# display_driver_rev_B.net
KiCad netlist of a schematic drawn in EAGLE
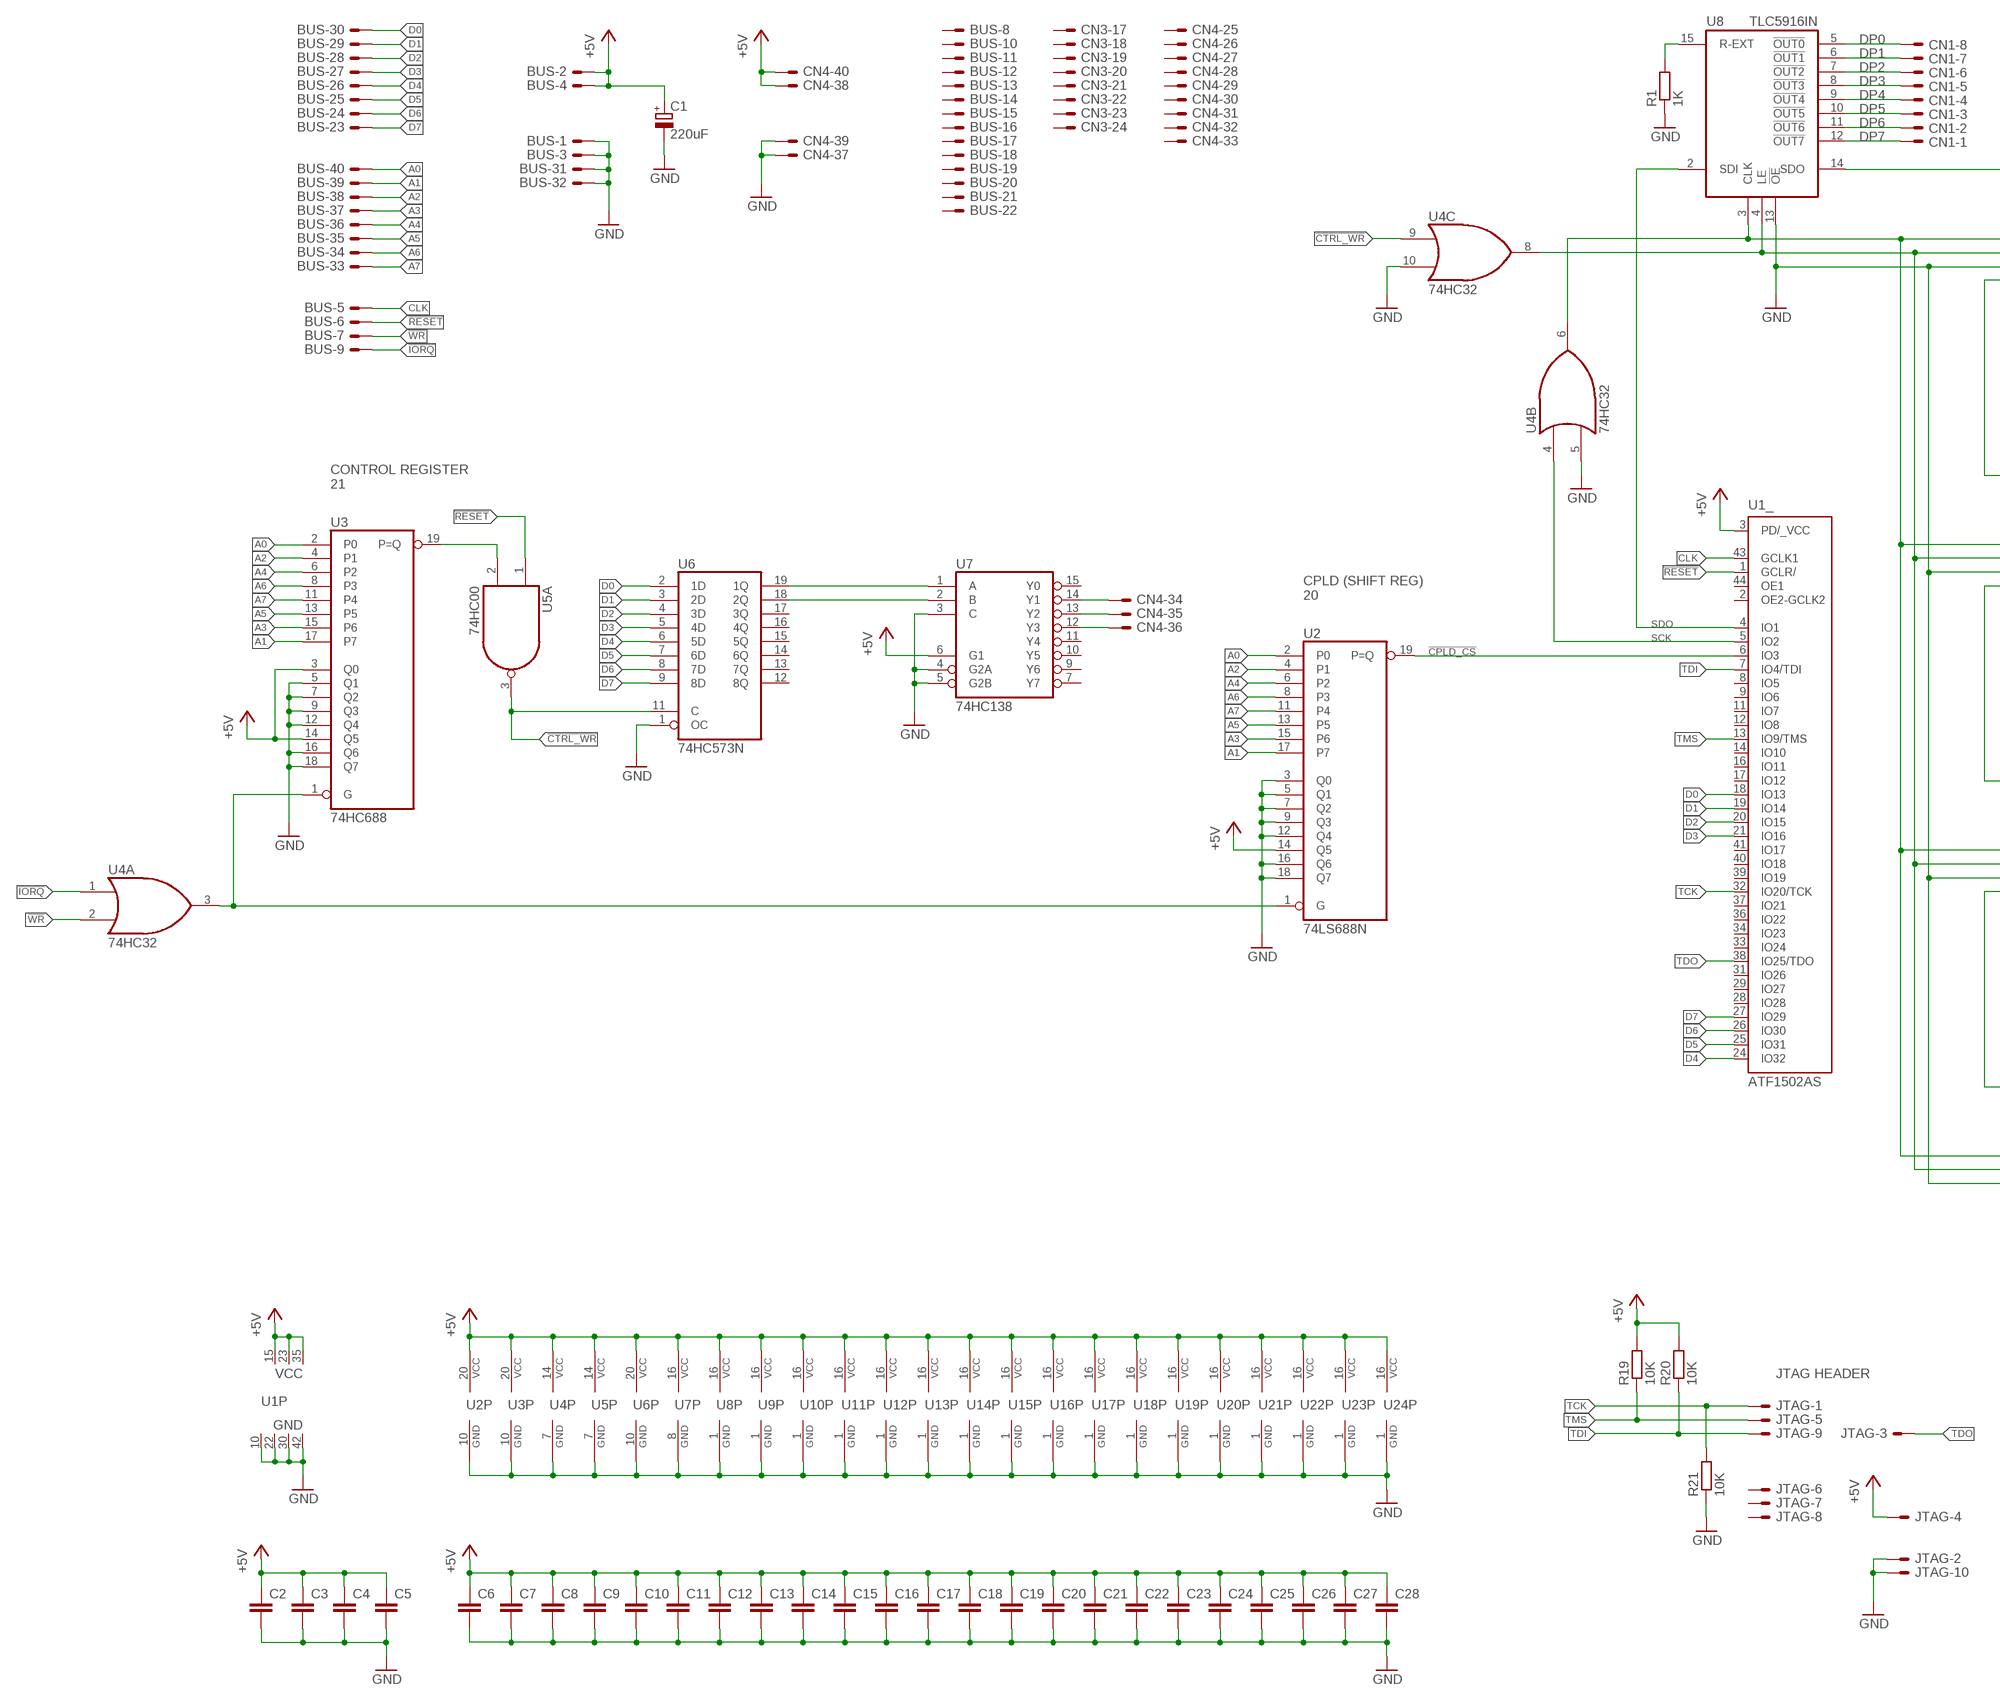
[diagram p0: schematic, sheet 1, part 1 of 2]
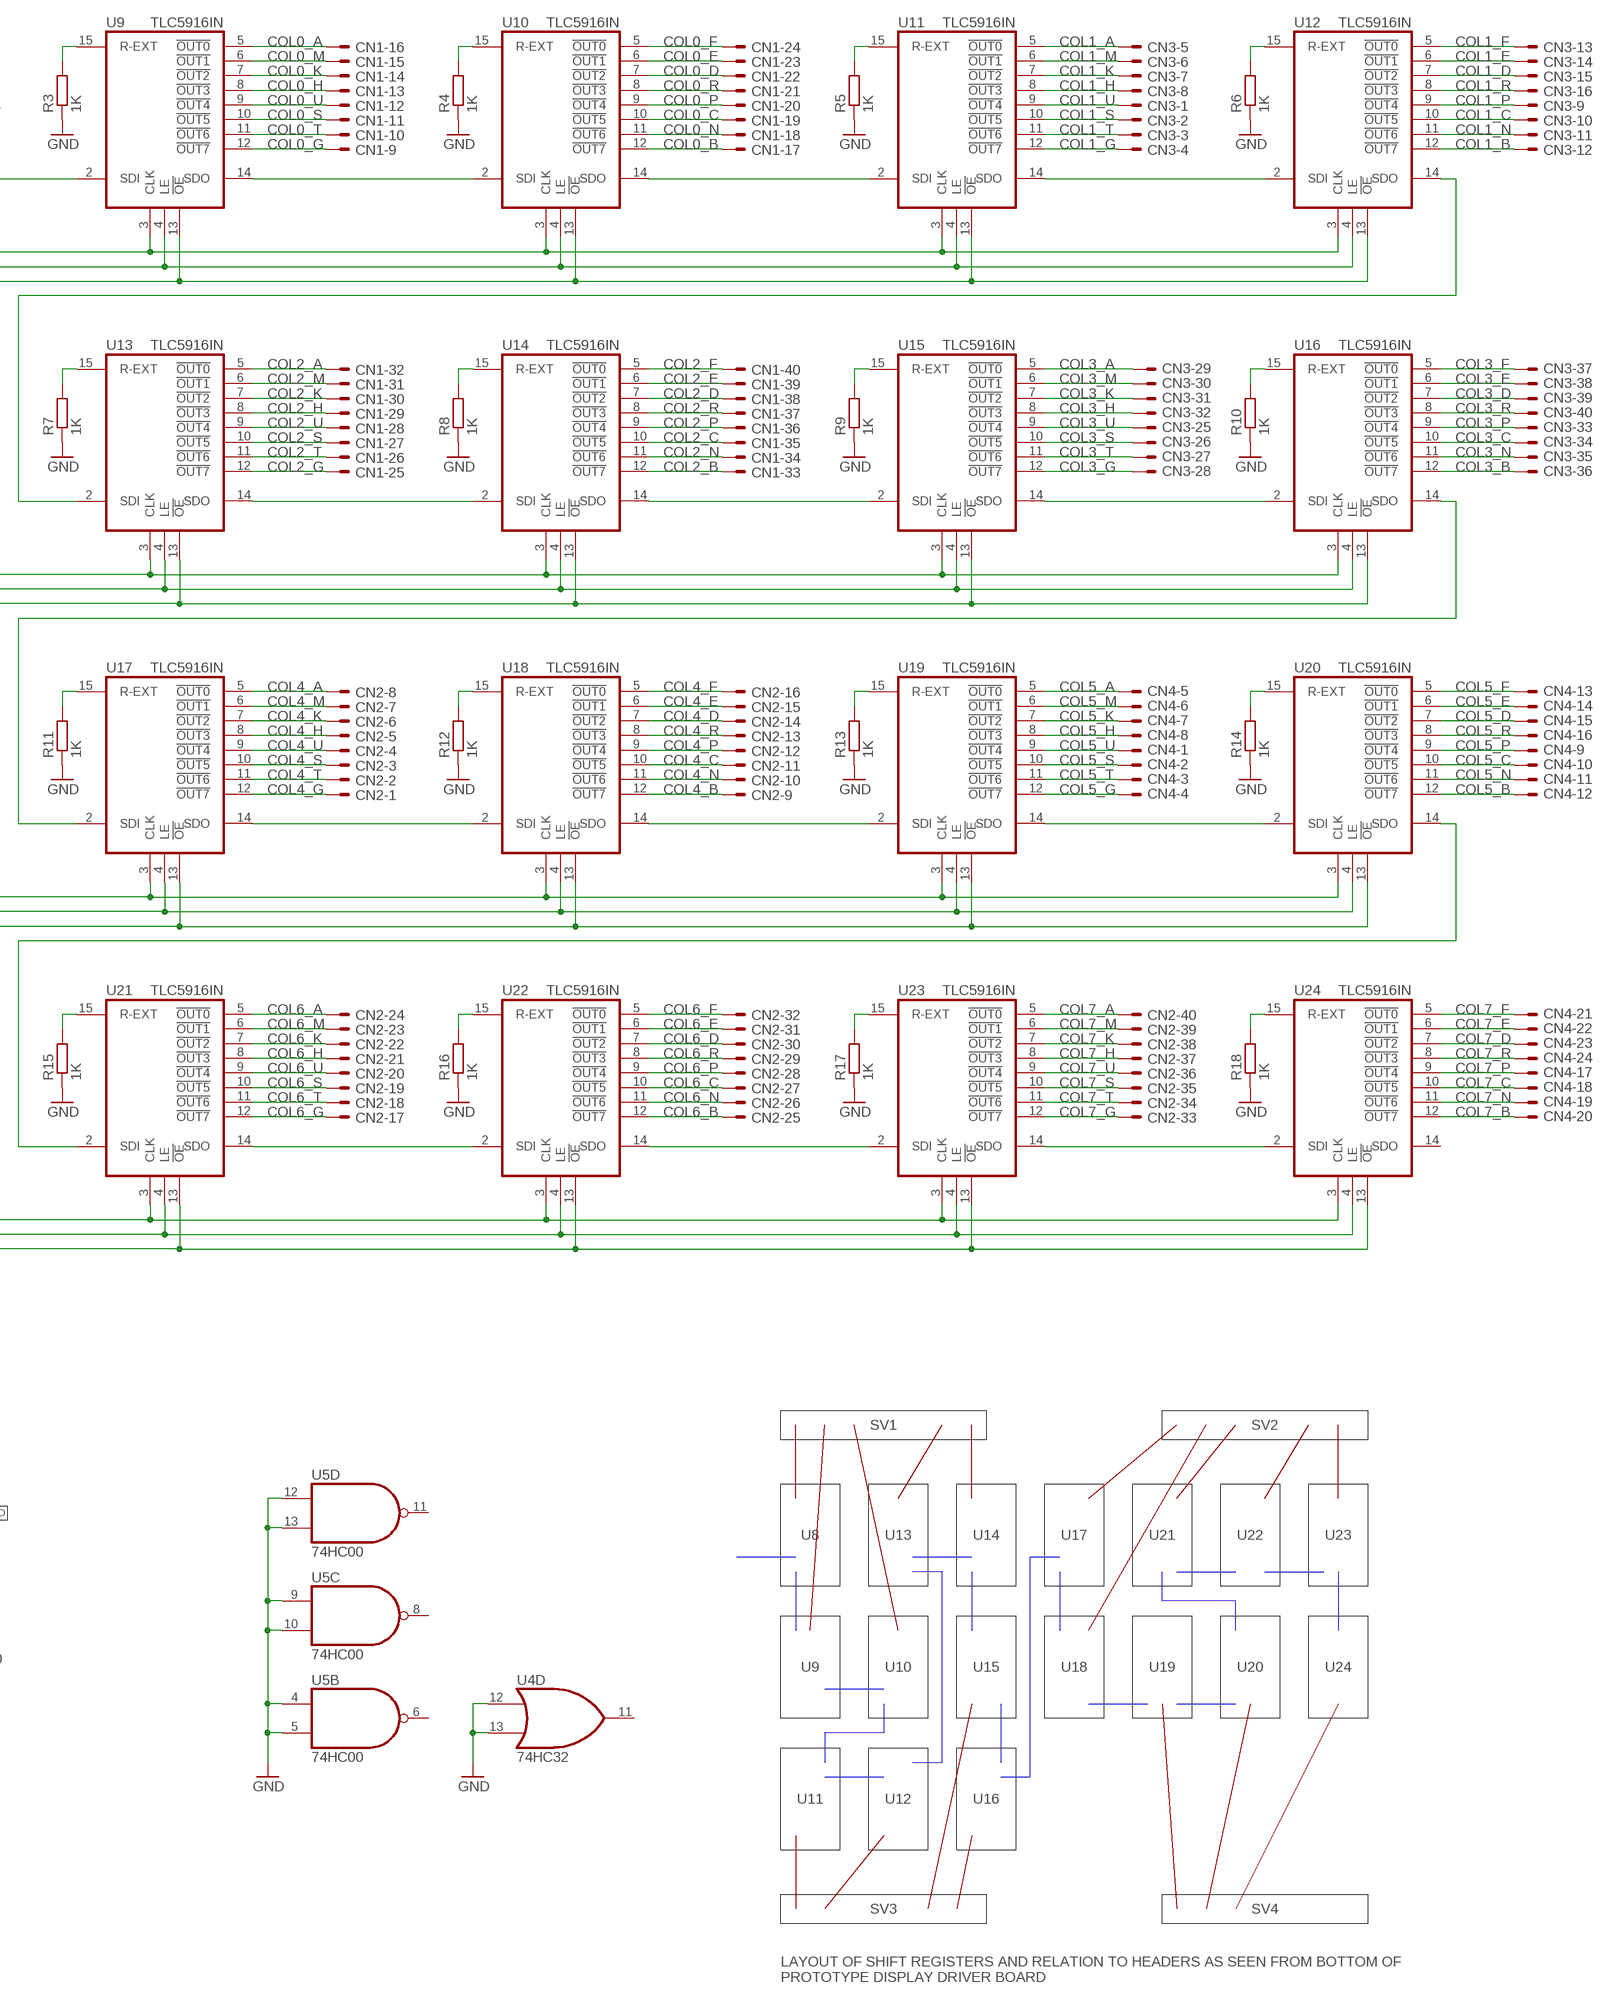
[diagram p1: schematic, sheet 1, part 2 of 2]

(export (version "E")
  (design (tool "Eeschema 10.0.6"))
  (components
    (comp (ref "BUS")
      (value "HDR40")
      (footprint "eagle-import:HDR40")
      (libsource (lib "eagle-import") (part "HDR40"))
    )
    (comp (ref "C1")
      (value "220uF")
      (footprint "eagle-import:E3,5-8")
      (libsource (lib "eagle-import") (part "CPOL-EUE3.5-8"))
    )
    (comp (ref "C2")
      (value "C-EU050-025X075")
      (footprint "eagle-import:C050-025X075")
      (libsource (lib "eagle-import") (part "C-EU050-025X075"))
    )
    (comp (ref "C3")
      (value "C-EU050-025X075")
      (footprint "eagle-import:C050-025X075")
      (libsource (lib "eagle-import") (part "C-EU050-025X075"))
    )
    (comp (ref "C4")
      (value "C-EU050-025X075")
      (footprint "eagle-import:C050-025X075")
      (libsource (lib "eagle-import") (part "C-EU050-025X075"))
    )
    (comp (ref "C5")
      (value "C-EU050-025X075")
      (footprint "eagle-import:C050-025X075")
      (libsource (lib "eagle-import") (part "C-EU050-025X075"))
    )
    (comp (ref "C6")
      (value "C-EU050-025X075")
      (footprint "eagle-import:C050-025X075")
      (libsource (lib "eagle-import") (part "C-EU050-025X075"))
    )
    (comp (ref "C7")
      (value "C-EU050-025X075")
      (footprint "eagle-import:C050-025X075")
      (libsource (lib "eagle-import") (part "C-EU050-025X075"))
    )
    (comp (ref "C8")
      (value "C-EU050-025X075")
      (footprint "eagle-import:C050-025X075")
      (libsource (lib "eagle-import") (part "C-EU050-025X075"))
    )
    (comp (ref "C9")
      (value "C-EU050-025X075")
      (footprint "eagle-import:C050-025X075")
      (libsource (lib "eagle-import") (part "C-EU050-025X075"))
    )
    (comp (ref "C10")
      (value "C-EU050-025X075")
      (footprint "eagle-import:C050-025X075")
      (libsource (lib "eagle-import") (part "C-EU050-025X075"))
    )
    (comp (ref "C11")
      (value "C-EU050-025X075")
      (footprint "eagle-import:C050-025X075")
      (libsource (lib "eagle-import") (part "C-EU050-025X075"))
    )
    (comp (ref "C12")
      (value "C-EU050-025X075")
      (footprint "eagle-import:C050-025X075")
      (libsource (lib "eagle-import") (part "C-EU050-025X075"))
    )
    (comp (ref "C13")
      (value "C-EU050-025X075")
      (footprint "eagle-import:C050-025X075")
      (libsource (lib "eagle-import") (part "C-EU050-025X075"))
    )
    (comp (ref "C14")
      (value "C-EU050-025X075")
      (footprint "eagle-import:C050-025X075")
      (libsource (lib "eagle-import") (part "C-EU050-025X075"))
    )
    (comp (ref "C15")
      (value "C-EU050-025X075")
      (footprint "eagle-import:C050-025X075")
      (libsource (lib "eagle-import") (part "C-EU050-025X075"))
    )
    (comp (ref "C16")
      (value "C-EU050-025X075")
      (footprint "eagle-import:C050-025X075")
      (libsource (lib "eagle-import") (part "C-EU050-025X075"))
    )
    (comp (ref "C17")
      (value "C-EU050-025X075")
      (footprint "eagle-import:C050-025X075")
      (libsource (lib "eagle-import") (part "C-EU050-025X075"))
    )
    (comp (ref "C18")
      (value "C-EU050-025X075")
      (footprint "eagle-import:C050-025X075")
      (libsource (lib "eagle-import") (part "C-EU050-025X075"))
    )
    (comp (ref "C19")
      (value "C-EU050-025X075")
      (footprint "eagle-import:C050-025X075")
      (libsource (lib "eagle-import") (part "C-EU050-025X075"))
    )
    (comp (ref "C20")
      (value "C-EU050-025X075")
      (footprint "eagle-import:C050-025X075")
      (libsource (lib "eagle-import") (part "C-EU050-025X075"))
    )
    (comp (ref "C21")
      (value "C-EU050-025X075")
      (footprint "eagle-import:C050-025X075")
      (libsource (lib "eagle-import") (part "C-EU050-025X075"))
    )
    (comp (ref "C22")
      (value "C-EU050-025X075")
      (footprint "eagle-import:C050-025X075")
      (libsource (lib "eagle-import") (part "C-EU050-025X075"))
    )
    (comp (ref "C23")
      (value "C-EU050-025X075")
      (footprint "eagle-import:C050-025X075")
      (libsource (lib "eagle-import") (part "C-EU050-025X075"))
    )
    (comp (ref "C24")
      (value "C-EU050-025X075")
      (footprint "eagle-import:C050-025X075")
      (libsource (lib "eagle-import") (part "C-EU050-025X075"))
    )
    (comp (ref "C25")
      (value "C-EU050-025X075")
      (footprint "eagle-import:C050-025X075")
      (libsource (lib "eagle-import") (part "C-EU050-025X075"))
    )
    (comp (ref "C26")
      (value "C-EU050-025X075")
      (footprint "eagle-import:C050-025X075")
      (libsource (lib "eagle-import") (part "C-EU050-025X075"))
    )
    (comp (ref "C27")
      (value "C-EU050-025X075")
      (footprint "eagle-import:C050-025X075")
      (libsource (lib "eagle-import") (part "C-EU050-025X075"))
    )
    (comp (ref "C28")
      (value "C-EU050-025X075")
      (footprint "eagle-import:C050-025X075")
      (libsource (lib "eagle-import") (part "C-EU050-025X075"))
    )
    (comp (ref "CN1")
      (value "HDR40")
      (footprint "eagle-import:HDR40")
      (libsource (lib "eagle-import") (part "HDR40"))
    )
    (comp (ref "CN2")
      (value "HDR40")
      (footprint "eagle-import:HDR40")
      (libsource (lib "eagle-import") (part "HDR40"))
    )
    (comp (ref "CN3")
      (value "HDR40")
      (footprint "eagle-import:HDR40")
      (libsource (lib "eagle-import") (part "HDR40"))
    )
    (comp (ref "CN4")
      (value "HDR40")
      (footprint "eagle-import:HDR40")
      (libsource (lib "eagle-import") (part "HDR40"))
    )
    (comp (ref "JTAG")
      (value "ML10E")
      (footprint "eagle-import:ML10")
      (libsource (lib "eagle-import") (part "ML10E"))
    )
    (comp (ref "R1")
      (value "1K")
      (footprint "eagle-import:0207_10")
      (libsource (lib "eagle-import") (part "R-EU_0207/10"))
    )
    (comp (ref "R3")
      (value "1K")
      (footprint "eagle-import:0207_10")
      (libsource (lib "eagle-import") (part "R-EU_0207/10"))
    )
    (comp (ref "R4")
      (value "1K")
      (footprint "eagle-import:0207_10")
      (libsource (lib "eagle-import") (part "R-EU_0207/10"))
    )
    (comp (ref "R5")
      (value "1K")
      (footprint "eagle-import:0207_10")
      (libsource (lib "eagle-import") (part "R-EU_0207/10"))
    )
    (comp (ref "R6")
      (value "1K")
      (footprint "eagle-import:0207_10")
      (libsource (lib "eagle-import") (part "R-EU_0207/10"))
    )
    (comp (ref "R7")
      (value "1K")
      (footprint "eagle-import:0207_10")
      (libsource (lib "eagle-import") (part "R-EU_0207/10"))
    )
    (comp (ref "R8")
      (value "1K")
      (footprint "eagle-import:0207_10")
      (libsource (lib "eagle-import") (part "R-EU_0207/10"))
    )
    (comp (ref "R9")
      (value "1K")
      (footprint "eagle-import:0207_10")
      (libsource (lib "eagle-import") (part "R-EU_0207/10"))
    )
    (comp (ref "R10")
      (value "1K")
      (footprint "eagle-import:0207_10")
      (libsource (lib "eagle-import") (part "R-EU_0207/10"))
    )
    (comp (ref "R11")
      (value "1K")
      (footprint "eagle-import:0207_10")
      (libsource (lib "eagle-import") (part "R-EU_0207/10"))
    )
    (comp (ref "R12")
      (value "1K")
      (footprint "eagle-import:0207_10")
      (libsource (lib "eagle-import") (part "R-EU_0207/10"))
    )
    (comp (ref "R13")
      (value "1K")
      (footprint "eagle-import:0207_10")
      (libsource (lib "eagle-import") (part "R-EU_0207/10"))
    )
    (comp (ref "R14")
      (value "1K")
      (footprint "eagle-import:0207_10")
      (libsource (lib "eagle-import") (part "R-EU_0207/10"))
    )
    (comp (ref "R15")
      (value "1K")
      (footprint "eagle-import:0207_10")
      (libsource (lib "eagle-import") (part "R-EU_0207/10"))
    )
    (comp (ref "R16")
      (value "1K")
      (footprint "eagle-import:0207_10")
      (libsource (lib "eagle-import") (part "R-EU_0207/10"))
    )
    (comp (ref "R17")
      (value "1K")
      (footprint "eagle-import:0207_10")
      (libsource (lib "eagle-import") (part "R-EU_0207/10"))
    )
    (comp (ref "R18")
      (value "1K")
      (footprint "eagle-import:0207_10")
      (libsource (lib "eagle-import") (part "R-EU_0207/10"))
    )
    (comp (ref "R19")
      (value "10K")
      (footprint "eagle-import:0207_10")
      (libsource (lib "eagle-import") (part "R-EU_0207/10"))
    )
    (comp (ref "R20")
      (value "10K")
      (footprint "eagle-import:0207_10")
      (libsource (lib "eagle-import") (part "R-EU_0207/10"))
    )
    (comp (ref "R21")
      (value "10K")
      (footprint "eagle-import:0207_10")
      (libsource (lib "eagle-import") (part "R-EU_0207/10"))
    )
    (comp (ref "U1")
      (value "ATF1502AS")
      (footprint "eagle-import:PLCC-S44")
      (fields (field (name "MPN") "EPM7032SLC44-6N"))
      (libsource (lib "eagle-import") (part "EPM7032S44"))
    )
    (comp (ref "U2")
      (value "74LS688N")
      (footprint "eagle-import:DIL20")
      (libsource (lib "eagle-import") (part "74688NLS"))
    )
    (comp (ref "U3")
      (value "74HC688")
      (footprint "eagle-import:DIL20")
      (libsource (lib "eagle-import") (part "74688NLS"))
    )
    (comp (ref "U4")
      (value "74HC32")
      (footprint "eagle-import:DIL14")
      (libsource (lib "eagle-import") (part "7432NLS"))
    )
    (comp (ref "U5")
      (value "74HC00")
      (footprint "eagle-import:DIL14")
      (libsource (lib "eagle-import") (part "7400NLS"))
    )
    (comp (ref "U6")
      (value "74HC573N")
      (footprint "eagle-import:DIL20")
      (libsource (lib "eagle-import") (part "74573NHC"))
    )
    (comp (ref "U7")
      (value "74HC138")
      (footprint "eagle-import:DIL16")
      (libsource (lib "eagle-import") (part "74138NLS"))
    )
    (comp (ref "U8")
      (value "TLC5916IN")
      (footprint "eagle-import:DIL16")
      (libsource (lib "eagle-import") (part "TLC5916IN"))
    )
    (comp (ref "U9")
      (value "TLC5916IN")
      (footprint "eagle-import:DIL16")
      (libsource (lib "eagle-import") (part "TLC5916IN"))
    )
    (comp (ref "U10")
      (value "TLC5916IN")
      (footprint "eagle-import:DIL16")
      (libsource (lib "eagle-import") (part "TLC5916IN"))
    )
    (comp (ref "U11")
      (value "TLC5916IN")
      (footprint "eagle-import:DIL16")
      (libsource (lib "eagle-import") (part "TLC5916IN"))
    )
    (comp (ref "U12")
      (value "TLC5916IN")
      (footprint "eagle-import:DIL16")
      (libsource (lib "eagle-import") (part "TLC5916IN"))
    )
    (comp (ref "U13")
      (value "TLC5916IN")
      (footprint "eagle-import:DIL16")
      (libsource (lib "eagle-import") (part "TLC5916IN"))
    )
    (comp (ref "U14")
      (value "TLC5916IN")
      (footprint "eagle-import:DIL16")
      (libsource (lib "eagle-import") (part "TLC5916IN"))
    )
    (comp (ref "U15")
      (value "TLC5916IN")
      (footprint "eagle-import:DIL16")
      (libsource (lib "eagle-import") (part "TLC5916IN"))
    )
    (comp (ref "U16")
      (value "TLC5916IN")
      (footprint "eagle-import:DIL16")
      (libsource (lib "eagle-import") (part "TLC5916IN"))
    )
    (comp (ref "U17")
      (value "TLC5916IN")
      (footprint "eagle-import:DIL16")
      (libsource (lib "eagle-import") (part "TLC5916IN"))
    )
    (comp (ref "U18")
      (value "TLC5916IN")
      (footprint "eagle-import:DIL16")
      (libsource (lib "eagle-import") (part "TLC5916IN"))
    )
    (comp (ref "U19")
      (value "TLC5916IN")
      (footprint "eagle-import:DIL16")
      (libsource (lib "eagle-import") (part "TLC5916IN"))
    )
    (comp (ref "U20")
      (value "TLC5916IN")
      (footprint "eagle-import:DIL16")
      (libsource (lib "eagle-import") (part "TLC5916IN"))
    )
    (comp (ref "U21")
      (value "TLC5916IN")
      (footprint "eagle-import:DIL16")
      (libsource (lib "eagle-import") (part "TLC5916IN"))
    )
    (comp (ref "U22")
      (value "TLC5916IN")
      (footprint "eagle-import:DIL16")
      (libsource (lib "eagle-import") (part "TLC5916IN"))
    )
    (comp (ref "U23")
      (value "TLC5916IN")
      (footprint "eagle-import:DIL16")
      (libsource (lib "eagle-import") (part "TLC5916IN"))
    )
    (comp (ref "U24")
      (value "TLC5916IN")
      (footprint "eagle-import:DIL16")
      (libsource (lib "eagle-import") (part "TLC5916IN"))
    )
  )
  (nets
    (net (code "1") (name "+5V") (class "Default")
      (node (ref "BUS") (pin "2") (pinfunction "S_2") (pintype "passive"))
      (node (ref "BUS") (pin "4") (pinfunction "S_4") (pintype "passive"))
      (node (ref "C1") (pin "+") (pinfunction "+_+") (pintype "passive"))
      (node (ref "C10") (pin "1") (pinfunction "1_1") (pintype "passive"))
      (node (ref "C11") (pin "1") (pinfunction "1_1") (pintype "passive"))
      (node (ref "C12") (pin "1") (pinfunction "1_1") (pintype "passive"))
      (node (ref "C13") (pin "1") (pinfunction "1_1") (pintype "passive"))
      (node (ref "C14") (pin "1") (pinfunction "1_1") (pintype "passive"))
      (node (ref "C15") (pin "1") (pinfunction "1_1") (pintype "passive"))
      (node (ref "C16") (pin "1") (pinfunction "1_1") (pintype "passive"))
      (node (ref "C17") (pin "1") (pinfunction "1_1") (pintype "passive"))
      (node (ref "C18") (pin "1") (pinfunction "1_1") (pintype "passive"))
      (node (ref "C19") (pin "1") (pinfunction "1_1") (pintype "passive"))
      (node (ref "C2") (pin "1") (pinfunction "1_1") (pintype "passive"))
      (node (ref "C20") (pin "1") (pinfunction "1_1") (pintype "passive"))
      (node (ref "C21") (pin "1") (pinfunction "1_1") (pintype "passive"))
      (node (ref "C22") (pin "1") (pinfunction "1_1") (pintype "passive"))
      (node (ref "C23") (pin "1") (pinfunction "1_1") (pintype "passive"))
      (node (ref "C24") (pin "1") (pinfunction "1_1") (pintype "passive"))
      (node (ref "C25") (pin "1") (pinfunction "1_1") (pintype "passive"))
      (node (ref "C26") (pin "1") (pinfunction "1_1") (pintype "passive"))
      (node (ref "C27") (pin "1") (pinfunction "1_1") (pintype "passive"))
      (node (ref "C28") (pin "1") (pinfunction "1_1") (pintype "passive"))
      (node (ref "C3") (pin "1") (pinfunction "1_1") (pintype "passive"))
      (node (ref "C4") (pin "1") (pinfunction "1_1") (pintype "passive"))
      (node (ref "C5") (pin "1") (pinfunction "1_1") (pintype "passive"))
      (node (ref "C6") (pin "1") (pinfunction "1_1") (pintype "passive"))
      (node (ref "C7") (pin "1") (pinfunction "1_1") (pintype "passive"))
      (node (ref "C8") (pin "1") (pinfunction "1_1") (pintype "passive"))
      (node (ref "C9") (pin "1") (pinfunction "1_1") (pintype "passive"))
      (node (ref "CN4") (pin "38") (pinfunction "S_38") (pintype "passive"))
      (node (ref "CN4") (pin "40") (pinfunction "S_40") (pintype "passive"))
      (node (ref "JTAG") (pin "4") (pinfunction "S_4") (pintype "passive"))
      (node (ref "R19") (pin "2") (pinfunction "2_2") (pintype "passive"))
      (node (ref "R20") (pin "2") (pinfunction "2_2") (pintype "passive"))
      (node (ref "U1") (pin "15") (pinfunction "VCC_15") (pintype "power_in"))
      (node (ref "U1") (pin "23") (pinfunction "VCC_23") (pintype "power_in"))
      (node (ref "U1") (pin "3") (pinfunction "PD/_VCC_3") (pintype "passive"))
      (node (ref "U1") (pin "35") (pinfunction "VCC_35") (pintype "power_in"))
      (node (ref "U10") (pin "16") (pinfunction "VCC_16") (pintype "power_in"))
      (node (ref "U11") (pin "16") (pinfunction "VCC_16") (pintype "power_in"))
      (node (ref "U12") (pin "16") (pinfunction "VCC_16") (pintype "power_in"))
      (node (ref "U13") (pin "16") (pinfunction "VCC_16") (pintype "power_in"))
      (node (ref "U14") (pin "16") (pinfunction "VCC_16") (pintype "power_in"))
      (node (ref "U15") (pin "16") (pinfunction "VCC_16") (pintype "power_in"))
      (node (ref "U16") (pin "16") (pinfunction "VCC_16") (pintype "power_in"))
      (node (ref "U17") (pin "16") (pinfunction "VCC_16") (pintype "power_in"))
      (node (ref "U18") (pin "16") (pinfunction "VCC_16") (pintype "power_in"))
      (node (ref "U19") (pin "16") (pinfunction "VCC_16") (pintype "power_in"))
      (node (ref "U2") (pin "14") (pinfunction "Q5_14") (pintype "input"))
      (node (ref "U2") (pin "20") (pinfunction "VCC_20") (pintype "power_in"))
      (node (ref "U20") (pin "16") (pinfunction "VCC_16") (pintype "power_in"))
      (node (ref "U21") (pin "16") (pinfunction "VCC_16") (pintype "power_in"))
      (node (ref "U22") (pin "16") (pinfunction "VCC_16") (pintype "power_in"))
      (node (ref "U23") (pin "16") (pinfunction "VCC_16") (pintype "power_in"))
      (node (ref "U24") (pin "16") (pinfunction "VCC_16") (pintype "power_in"))
      (node (ref "U3") (pin "14") (pinfunction "Q5_14") (pintype "input"))
      (node (ref "U3") (pin "20") (pinfunction "VCC_20") (pintype "power_in"))
      (node (ref "U3") (pin "3") (pinfunction "Q0_3") (pintype "input"))
      (node (ref "U4") (pin "14") (pinfunction "VCC_14") (pintype "power_in"))
      (node (ref "U5") (pin "14") (pinfunction "VCC_14") (pintype "power_in"))
      (node (ref "U6") (pin "20") (pinfunction "VCC_20") (pintype "power_in"))
      (node (ref "U7") (pin "16") (pinfunction "VCC_16") (pintype "power_in"))
      (node (ref "U7") (pin "6") (pinfunction "G1_6") (pintype "input"))
      (node (ref "U8") (pin "16") (pinfunction "VCC_16") (pintype "power_in"))
      (node (ref "U9") (pin "16") (pinfunction "VCC_16") (pintype "power_in"))
    )
    (net (code "2") (name "/COL0_A") (class "Default")
      (node (ref "CN1") (pin "16") (pinfunction "S_16") (pintype "passive"))
      (node (ref "U9") (pin "5") (pinfunction "~{OUT0}_5") (pintype "open_collector"))
    )
    (net (code "3") (name "/COL0_B") (class "Default")
      (node (ref "CN1") (pin "17") (pinfunction "S_17") (pintype "passive"))
      (node (ref "U10") (pin "12") (pinfunction "~{OUT7}_12") (pintype "open_collector"))
    )
    (net (code "4") (name "/COL0_C") (class "Default")
      (node (ref "CN1") (pin "19") (pinfunction "S_19") (pintype "passive"))
      (node (ref "U10") (pin "10") (pinfunction "~{OUT5}_10") (pintype "open_collector"))
    )
    (net (code "5") (name "/COL0_D") (class "Default")
      (node (ref "CN1") (pin "22") (pinfunction "S_22") (pintype "passive"))
      (node (ref "U10") (pin "7") (pinfunction "~{OUT2}_7") (pintype "open_collector"))
    )
    (net (code "6") (name "/COL0_E") (class "Default")
      (node (ref "CN1") (pin "23") (pinfunction "S_23") (pintype "passive"))
      (node (ref "U10") (pin "6") (pinfunction "~{OUT1}_6") (pintype "open_collector"))
    )
    (net (code "7") (name "/COL0_F") (class "Default")
      (node (ref "CN1") (pin "24") (pinfunction "S_24") (pintype "passive"))
      (node (ref "U10") (pin "5") (pinfunction "~{OUT0}_5") (pintype "open_collector"))
    )
    (net (code "8") (name "/COL0_G") (class "Default")
      (node (ref "CN1") (pin "9") (pinfunction "S_9") (pintype "passive"))
      (node (ref "U9") (pin "12") (pinfunction "~{OUT7}_12") (pintype "open_collector"))
    )
    (net (code "9") (name "/COL0_H") (class "Default")
      (node (ref "CN1") (pin "13") (pinfunction "S_13") (pintype "passive"))
      (node (ref "U9") (pin "8") (pinfunction "~{OUT3}_8") (pintype "open_collector"))
    )
    (net (code "10") (name "/COL0_K") (class "Default")
      (node (ref "CN1") (pin "14") (pinfunction "S_14") (pintype "passive"))
      (node (ref "U9") (pin "7") (pinfunction "~{OUT2}_7") (pintype "open_collector"))
    )
    (net (code "11") (name "/COL0_M") (class "Default")
      (node (ref "CN1") (pin "15") (pinfunction "S_15") (pintype "passive"))
      (node (ref "U9") (pin "6") (pinfunction "~{OUT1}_6") (pintype "open_collector"))
    )
    (net (code "12") (name "/COL0_N") (class "Default")
      (node (ref "CN1") (pin "18") (pinfunction "S_18") (pintype "passive"))
      (node (ref "U10") (pin "11") (pinfunction "~{OUT6}_11") (pintype "open_collector"))
    )
    (net (code "13") (name "/COL0_P") (class "Default")
      (node (ref "CN1") (pin "20") (pinfunction "S_20") (pintype "passive"))
      (node (ref "U10") (pin "9") (pinfunction "~{OUT4}_9") (pintype "open_collector"))
    )
    (net (code "14") (name "/COL0_R") (class "Default")
      (node (ref "CN1") (pin "21") (pinfunction "S_21") (pintype "passive"))
      (node (ref "U10") (pin "8") (pinfunction "~{OUT3}_8") (pintype "open_collector"))
    )
    (net (code "15") (name "/COL0_S") (class "Default")
      (node (ref "CN1") (pin "11") (pinfunction "S_11") (pintype "passive"))
      (node (ref "U9") (pin "10") (pinfunction "~{OUT5}_10") (pintype "open_collector"))
    )
    (net (code "16") (name "/COL0_T") (class "Default")
      (node (ref "CN1") (pin "10") (pinfunction "S_10") (pintype "passive"))
      (node (ref "U9") (pin "11") (pinfunction "~{OUT6}_11") (pintype "open_collector"))
    )
    (net (code "17") (name "/COL0_U") (class "Default")
      (node (ref "CN1") (pin "12") (pinfunction "S_12") (pintype "passive"))
      (node (ref "U9") (pin "9") (pinfunction "~{OUT4}_9") (pintype "open_collector"))
    )
    (net (code "18") (name "/COL1_A") (class "Default")
      (node (ref "CN3") (pin "5") (pinfunction "S_5") (pintype "passive"))
      (node (ref "U11") (pin "5") (pinfunction "~{OUT0}_5") (pintype "open_collector"))
    )
    (net (code "19") (name "/COL1_B") (class "Default")
      (node (ref "CN3") (pin "12") (pinfunction "S_12") (pintype "passive"))
      (node (ref "U12") (pin "12") (pinfunction "~{OUT7}_12") (pintype "open_collector"))
    )
    (net (code "20") (name "/COL1_C") (class "Default")
      (node (ref "CN3") (pin "10") (pinfunction "S_10") (pintype "passive"))
      (node (ref "U12") (pin "10") (pinfunction "~{OUT5}_10") (pintype "open_collector"))
    )
    (net (code "21") (name "/COL1_D") (class "Default")
      (node (ref "CN3") (pin "15") (pinfunction "S_15") (pintype "passive"))
      (node (ref "U12") (pin "7") (pinfunction "~{OUT2}_7") (pintype "open_collector"))
    )
    (net (code "22") (name "/COL1_E") (class "Default")
      (node (ref "CN3") (pin "14") (pinfunction "S_14") (pintype "passive"))
      (node (ref "U12") (pin "6") (pinfunction "~{OUT1}_6") (pintype "open_collector"))
    )
    (net (code "23") (name "/COL1_F") (class "Default")
      (node (ref "CN3") (pin "13") (pinfunction "S_13") (pintype "passive"))
      (node (ref "U12") (pin "5") (pinfunction "~{OUT0}_5") (pintype "open_collector"))
    )
    (net (code "24") (name "/COL1_G") (class "Default")
      (node (ref "CN3") (pin "4") (pinfunction "S_4") (pintype "passive"))
      (node (ref "U11") (pin "12") (pinfunction "~{OUT7}_12") (pintype "open_collector"))
    )
    (net (code "25") (name "/COL1_H") (class "Default")
      (node (ref "CN3") (pin "8") (pinfunction "S_8") (pintype "passive"))
      (node (ref "U11") (pin "8") (pinfunction "~{OUT3}_8") (pintype "open_collector"))
    )
    (net (code "26") (name "/COL1_K") (class "Default")
      (node (ref "CN3") (pin "7") (pinfunction "S_7") (pintype "passive"))
      (node (ref "U11") (pin "7") (pinfunction "~{OUT2}_7") (pintype "open_collector"))
    )
    (net (code "27") (name "/COL1_M") (class "Default")
      (node (ref "CN3") (pin "6") (pinfunction "S_6") (pintype "passive"))
      (node (ref "U11") (pin "6") (pinfunction "~{OUT1}_6") (pintype "open_collector"))
    )
    (net (code "28") (name "/COL1_N") (class "Default")
      (node (ref "CN3") (pin "11") (pinfunction "S_11") (pintype "passive"))
      (node (ref "U12") (pin "11") (pinfunction "~{OUT6}_11") (pintype "open_collector"))
    )
    (net (code "29") (name "/COL1_P") (class "Default")
      (node (ref "CN3") (pin "9") (pinfunction "S_9") (pintype "passive"))
      (node (ref "U12") (pin "9") (pinfunction "~{OUT4}_9") (pintype "open_collector"))
    )
    (net (code "30") (name "/COL1_R") (class "Default")
      (node (ref "CN3") (pin "16") (pinfunction "S_16") (pintype "passive"))
      (node (ref "U12") (pin "8") (pinfunction "~{OUT3}_8") (pintype "open_collector"))
    )
    (net (code "31") (name "/COL1_S") (class "Default")
      (node (ref "CN3") (pin "2") (pinfunction "S_2") (pintype "passive"))
      (node (ref "U11") (pin "10") (pinfunction "~{OUT5}_10") (pintype "open_collector"))
    )
    (net (code "32") (name "/COL1_T") (class "Default")
      (node (ref "CN3") (pin "3") (pinfunction "S_3") (pintype "passive"))
      (node (ref "U11") (pin "11") (pinfunction "~{OUT6}_11") (pintype "open_collector"))
    )
    (net (code "33") (name "/COL1_U") (class "Default")
      (node (ref "CN3") (pin "1") (pinfunction "S_1") (pintype "passive"))
      (node (ref "U11") (pin "9") (pinfunction "~{OUT4}_9") (pintype "open_collector"))
    )
    (net (code "34") (name "/COL2_A") (class "Default")
      (node (ref "CN1") (pin "32") (pinfunction "S_32") (pintype "passive"))
      (node (ref "U13") (pin "5") (pinfunction "~{OUT0}_5") (pintype "open_collector"))
    )
    (net (code "35") (name "/COL2_B") (class "Default")
      (node (ref "CN1") (pin "33") (pinfunction "S_33") (pintype "passive"))
      (node (ref "U14") (pin "12") (pinfunction "~{OUT7}_12") (pintype "open_collector"))
    )
    (net (code "36") (name "/COL2_C") (class "Default")
      (node (ref "CN1") (pin "35") (pinfunction "S_35") (pintype "passive"))
      (node (ref "U14") (pin "10") (pinfunction "~{OUT5}_10") (pintype "open_collector"))
    )
    (net (code "37") (name "/COL2_D") (class "Default")
      (node (ref "CN1") (pin "38") (pinfunction "S_38") (pintype "passive"))
      (node (ref "U14") (pin "7") (pinfunction "~{OUT2}_7") (pintype "open_collector"))
    )
    (net (code "38") (name "/COL2_E") (class "Default")
      (node (ref "CN1") (pin "39") (pinfunction "S_39") (pintype "passive"))
      (node (ref "U14") (pin "6") (pinfunction "~{OUT1}_6") (pintype "open_collector"))
    )
    (net (code "39") (name "/COL2_F") (class "Default")
      (node (ref "CN1") (pin "40") (pinfunction "S_40") (pintype "passive"))
      (node (ref "U14") (pin "5") (pinfunction "~{OUT0}_5") (pintype "open_collector"))
    )
    (net (code "40") (name "/COL2_G") (class "Default")
      (node (ref "CN1") (pin "25") (pinfunction "S_25") (pintype "passive"))
      (node (ref "U13") (pin "12") (pinfunction "~{OUT7}_12") (pintype "open_collector"))
    )
    (net (code "41") (name "/COL2_H") (class "Default")
      (node (ref "CN1") (pin "29") (pinfunction "S_29") (pintype "passive"))
      (node (ref "U13") (pin "8") (pinfunction "~{OUT3}_8") (pintype "open_collector"))
    )
    (net (code "42") (name "/COL2_K") (class "Default")
      (node (ref "CN1") (pin "30") (pinfunction "S_30") (pintype "passive"))
      (node (ref "U13") (pin "7") (pinfunction "~{OUT2}_7") (pintype "open_collector"))
    )
    (net (code "43") (name "/COL2_M") (class "Default")
      (node (ref "CN1") (pin "31") (pinfunction "S_31") (pintype "passive"))
      (node (ref "U13") (pin "6") (pinfunction "~{OUT1}_6") (pintype "open_collector"))
    )
    (net (code "44") (name "/COL2_N") (class "Default")
      (node (ref "CN1") (pin "34") (pinfunction "S_34") (pintype "passive"))
      (node (ref "U14") (pin "11") (pinfunction "~{OUT6}_11") (pintype "open_collector"))
    )
    (net (code "45") (name "/COL2_P") (class "Default")
      (node (ref "CN1") (pin "36") (pinfunction "S_36") (pintype "passive"))
      (node (ref "U14") (pin "9") (pinfunction "~{OUT4}_9") (pintype "open_collector"))
    )
    (net (code "46") (name "/COL2_R") (class "Default")
      (node (ref "CN1") (pin "37") (pinfunction "S_37") (pintype "passive"))
      (node (ref "U14") (pin "8") (pinfunction "~{OUT3}_8") (pintype "open_collector"))
    )
    (net (code "47") (name "/COL2_S") (class "Default")
      (node (ref "CN1") (pin "27") (pinfunction "S_27") (pintype "passive"))
      (node (ref "U13") (pin "10") (pinfunction "~{OUT5}_10") (pintype "open_collector"))
    )
    (net (code "48") (name "/COL2_T") (class "Default")
      (node (ref "CN1") (pin "26") (pinfunction "S_26") (pintype "passive"))
      (node (ref "U13") (pin "11") (pinfunction "~{OUT6}_11") (pintype "open_collector"))
    )
    (net (code "49") (name "/COL2_U") (class "Default")
      (node (ref "CN1") (pin "28") (pinfunction "S_28") (pintype "passive"))
      (node (ref "U13") (pin "9") (pinfunction "~{OUT4}_9") (pintype "open_collector"))
    )
    (net (code "50") (name "/COL3_A") (class "Default")
      (node (ref "CN3") (pin "29") (pinfunction "S_29") (pintype "passive"))
      (node (ref "U15") (pin "5") (pinfunction "~{OUT0}_5") (pintype "open_collector"))
    )
    (net (code "51") (name "/COL3_B") (class "Default")
      (node (ref "CN3") (pin "36") (pinfunction "S_36") (pintype "passive"))
      (node (ref "U16") (pin "12") (pinfunction "~{OUT7}_12") (pintype "open_collector"))
    )
    (net (code "52") (name "/COL3_C") (class "Default")
      (node (ref "CN3") (pin "34") (pinfunction "S_34") (pintype "passive"))
      (node (ref "U16") (pin "10") (pinfunction "~{OUT5}_10") (pintype "open_collector"))
    )
    (net (code "53") (name "/COL3_D") (class "Default")
      (node (ref "CN3") (pin "39") (pinfunction "S_39") (pintype "passive"))
      (node (ref "U16") (pin "7") (pinfunction "~{OUT2}_7") (pintype "open_collector"))
    )
    (net (code "54") (name "/COL3_E") (class "Default")
      (node (ref "CN3") (pin "38") (pinfunction "S_38") (pintype "passive"))
      (node (ref "U16") (pin "6") (pinfunction "~{OUT1}_6") (pintype "open_collector"))
    )
    (net (code "55") (name "/COL3_F") (class "Default")
      (node (ref "CN3") (pin "37") (pinfunction "S_37") (pintype "passive"))
      (node (ref "U16") (pin "5") (pinfunction "~{OUT0}_5") (pintype "open_collector"))
    )
    (net (code "56") (name "/COL3_G") (class "Default")
      (node (ref "CN3") (pin "28") (pinfunction "S_28") (pintype "passive"))
      (node (ref "U15") (pin "12") (pinfunction "~{OUT7}_12") (pintype "open_collector"))
    )
    (net (code "57") (name "/COL3_H") (class "Default")
      (node (ref "CN3") (pin "32") (pinfunction "S_32") (pintype "passive"))
      (node (ref "U15") (pin "8") (pinfunction "~{OUT3}_8") (pintype "open_collector"))
    )
    (net (code "58") (name "/COL3_K") (class "Default")
      (node (ref "CN3") (pin "31") (pinfunction "S_31") (pintype "passive"))
      (node (ref "U15") (pin "7") (pinfunction "~{OUT2}_7") (pintype "open_collector"))
    )
    (net (code "59") (name "/COL3_M") (class "Default")
      (node (ref "CN3") (pin "30") (pinfunction "S_30") (pintype "passive"))
      (node (ref "U15") (pin "6") (pinfunction "~{OUT1}_6") (pintype "open_collector"))
    )
    (net (code "60") (name "/COL3_N") (class "Default")
      (node (ref "CN3") (pin "35") (pinfunction "S_35") (pintype "passive"))
      (node (ref "U16") (pin "11") (pinfunction "~{OUT6}_11") (pintype "open_collector"))
    )
    (net (code "61") (name "/COL3_P") (class "Default")
      (node (ref "CN3") (pin "33") (pinfunction "S_33") (pintype "passive"))
      (node (ref "U16") (pin "9") (pinfunction "~{OUT4}_9") (pintype "open_collector"))
    )
    (net (code "62") (name "/COL3_R") (class "Default")
      (node (ref "CN3") (pin "40") (pinfunction "S_40") (pintype "passive"))
      (node (ref "U16") (pin "8") (pinfunction "~{OUT3}_8") (pintype "open_collector"))
    )
    (net (code "63") (name "/COL3_S") (class "Default")
      (node (ref "CN3") (pin "26") (pinfunction "S_26") (pintype "passive"))
      (node (ref "U15") (pin "10") (pinfunction "~{OUT5}_10") (pintype "open_collector"))
    )
    (net (code "64") (name "/COL3_T") (class "Default")
      (node (ref "CN3") (pin "27") (pinfunction "S_27") (pintype "passive"))
      (node (ref "U15") (pin "11") (pinfunction "~{OUT6}_11") (pintype "open_collector"))
    )
    (net (code "65") (name "/COL3_U") (class "Default")
      (node (ref "CN3") (pin "25") (pinfunction "S_25") (pintype "passive"))
      (node (ref "U15") (pin "9") (pinfunction "~{OUT4}_9") (pintype "open_collector"))
    )
    (net (code "66") (name "/COL4_A") (class "Default")
      (node (ref "CN2") (pin "8") (pinfunction "S_8") (pintype "passive"))
      (node (ref "U17") (pin "5") (pinfunction "~{OUT0}_5") (pintype "open_collector"))
    )
    (net (code "67") (name "/COL4_B") (class "Default")
      (node (ref "CN2") (pin "9") (pinfunction "S_9") (pintype "passive"))
      (node (ref "U18") (pin "12") (pinfunction "~{OUT7}_12") (pintype "open_collector"))
    )
    (net (code "68") (name "/COL4_C") (class "Default")
      (node (ref "CN2") (pin "11") (pinfunction "S_11") (pintype "passive"))
      (node (ref "U18") (pin "10") (pinfunction "~{OUT5}_10") (pintype "open_collector"))
    )
    (net (code "69") (name "/COL4_D") (class "Default")
      (node (ref "CN2") (pin "14") (pinfunction "S_14") (pintype "passive"))
      (node (ref "U18") (pin "7") (pinfunction "~{OUT2}_7") (pintype "open_collector"))
    )
    (net (code "70") (name "/COL4_E") (class "Default")
      (node (ref "CN2") (pin "15") (pinfunction "S_15") (pintype "passive"))
      (node (ref "U18") (pin "6") (pinfunction "~{OUT1}_6") (pintype "open_collector"))
    )
    (net (code "71") (name "/COL4_F") (class "Default")
      (node (ref "CN2") (pin "16") (pinfunction "S_16") (pintype "passive"))
      (node (ref "U18") (pin "5") (pinfunction "~{OUT0}_5") (pintype "open_collector"))
    )
    (net (code "72") (name "/COL4_G") (class "Default")
      (node (ref "CN2") (pin "1") (pinfunction "S_1") (pintype "passive"))
      (node (ref "U17") (pin "12") (pinfunction "~{OUT7}_12") (pintype "open_collector"))
    )
    (net (code "73") (name "/COL4_H") (class "Default")
      (node (ref "CN2") (pin "5") (pinfunction "S_5") (pintype "passive"))
      (node (ref "U17") (pin "8") (pinfunction "~{OUT3}_8") (pintype "open_collector"))
    )
    (net (code "74") (name "/COL4_K") (class "Default")
      (node (ref "CN2") (pin "6") (pinfunction "S_6") (pintype "passive"))
      (node (ref "U17") (pin "7") (pinfunction "~{OUT2}_7") (pintype "open_collector"))
    )
    (net (code "75") (name "/COL4_M") (class "Default")
      (node (ref "CN2") (pin "7") (pinfunction "S_7") (pintype "passive"))
      (node (ref "U17") (pin "6") (pinfunction "~{OUT1}_6") (pintype "open_collector"))
    )
    (net (code "76") (name "/COL4_N") (class "Default")
      (node (ref "CN2") (pin "10") (pinfunction "S_10") (pintype "passive"))
      (node (ref "U18") (pin "11") (pinfunction "~{OUT6}_11") (pintype "open_collector"))
    )
    (net (code "77") (name "/COL4_P") (class "Default")
      (node (ref "CN2") (pin "12") (pinfunction "S_12") (pintype "passive"))
      (node (ref "U18") (pin "9") (pinfunction "~{OUT4}_9") (pintype "open_collector"))
    )
    (net (code "78") (name "/COL4_R") (class "Default")
      (node (ref "CN2") (pin "13") (pinfunction "S_13") (pintype "passive"))
      (node (ref "U18") (pin "8") (pinfunction "~{OUT3}_8") (pintype "open_collector"))
    )
    (net (code "79") (name "/COL4_S") (class "Default")
      (node (ref "CN2") (pin "3") (pinfunction "S_3") (pintype "passive"))
      (node (ref "U17") (pin "10") (pinfunction "~{OUT5}_10") (pintype "open_collector"))
    )
    (net (code "80") (name "/COL4_T") (class "Default")
      (node (ref "CN2") (pin "2") (pinfunction "S_2") (pintype "passive"))
      (node (ref "U17") (pin "11") (pinfunction "~{OUT6}_11") (pintype "open_collector"))
    )
    (net (code "81") (name "/COL4_U") (class "Default")
      (node (ref "CN2") (pin "4") (pinfunction "S_4") (pintype "passive"))
      (node (ref "U17") (pin "9") (pinfunction "~{OUT4}_9") (pintype "open_collector"))
    )
    (net (code "82") (name "/COL5_A") (class "Default")
      (node (ref "CN4") (pin "5") (pinfunction "S_5") (pintype "passive"))
      (node (ref "U19") (pin "5") (pinfunction "~{OUT0}_5") (pintype "open_collector"))
    )
    (net (code "83") (name "/COL5_B") (class "Default")
      (node (ref "CN4") (pin "12") (pinfunction "S_12") (pintype "passive"))
      (node (ref "U20") (pin "12") (pinfunction "~{OUT7}_12") (pintype "open_collector"))
    )
    (net (code "84") (name "/COL5_C") (class "Default")
      (node (ref "CN4") (pin "10") (pinfunction "S_10") (pintype "passive"))
      (node (ref "U20") (pin "10") (pinfunction "~{OUT5}_10") (pintype "open_collector"))
    )
    (net (code "85") (name "/COL5_D") (class "Default")
      (node (ref "CN4") (pin "15") (pinfunction "S_15") (pintype "passive"))
      (node (ref "U20") (pin "7") (pinfunction "~{OUT2}_7") (pintype "open_collector"))
    )
    (net (code "86") (name "/COL5_E") (class "Default")
      (node (ref "CN4") (pin "14") (pinfunction "S_14") (pintype "passive"))
      (node (ref "U20") (pin "6") (pinfunction "~{OUT1}_6") (pintype "open_collector"))
    )
    (net (code "87") (name "/COL5_F") (class "Default")
      (node (ref "CN4") (pin "13") (pinfunction "S_13") (pintype "passive"))
      (node (ref "U20") (pin "5") (pinfunction "~{OUT0}_5") (pintype "open_collector"))
    )
    (net (code "88") (name "/COL5_G") (class "Default")
      (node (ref "CN4") (pin "4") (pinfunction "S_4") (pintype "passive"))
      (node (ref "U19") (pin "12") (pinfunction "~{OUT7}_12") (pintype "open_collector"))
    )
    (net (code "89") (name "/COL5_H") (class "Default")
      (node (ref "CN4") (pin "8") (pinfunction "S_8") (pintype "passive"))
      (node (ref "U19") (pin "8") (pinfunction "~{OUT3}_8") (pintype "open_collector"))
    )
    (net (code "90") (name "/COL5_K") (class "Default")
      (node (ref "CN4") (pin "7") (pinfunction "S_7") (pintype "passive"))
      (node (ref "U19") (pin "7") (pinfunction "~{OUT2}_7") (pintype "open_collector"))
    )
    (net (code "91") (name "/COL5_M") (class "Default")
      (node (ref "CN4") (pin "6") (pinfunction "S_6") (pintype "passive"))
      (node (ref "U19") (pin "6") (pinfunction "~{OUT1}_6") (pintype "open_collector"))
    )
    (net (code "92") (name "/COL5_N") (class "Default")
      (node (ref "CN4") (pin "11") (pinfunction "S_11") (pintype "passive"))
      (node (ref "U20") (pin "11") (pinfunction "~{OUT6}_11") (pintype "open_collector"))
    )
    (net (code "93") (name "/COL5_P") (class "Default")
      (node (ref "CN4") (pin "9") (pinfunction "S_9") (pintype "passive"))
      (node (ref "U20") (pin "9") (pinfunction "~{OUT4}_9") (pintype "open_collector"))
    )
    (net (code "94") (name "/COL5_R") (class "Default")
      (node (ref "CN4") (pin "16") (pinfunction "S_16") (pintype "passive"))
      (node (ref "U20") (pin "8") (pinfunction "~{OUT3}_8") (pintype "open_collector"))
    )
    (net (code "95") (name "/COL5_S") (class "Default")
      (node (ref "CN4") (pin "2") (pinfunction "S_2") (pintype "passive"))
      (node (ref "U19") (pin "10") (pinfunction "~{OUT5}_10") (pintype "open_collector"))
    )
    (net (code "96") (name "/COL5_T") (class "Default")
      (node (ref "CN4") (pin "3") (pinfunction "S_3") (pintype "passive"))
      (node (ref "U19") (pin "11") (pinfunction "~{OUT6}_11") (pintype "open_collector"))
    )
    (net (code "97") (name "/COL5_U") (class "Default")
      (node (ref "CN4") (pin "1") (pinfunction "S_1") (pintype "passive"))
      (node (ref "U19") (pin "9") (pinfunction "~{OUT4}_9") (pintype "open_collector"))
    )
    (net (code "98") (name "/COL6_A") (class "Default")
      (node (ref "CN2") (pin "24") (pinfunction "S_24") (pintype "passive"))
      (node (ref "U21") (pin "5") (pinfunction "~{OUT0}_5") (pintype "open_collector"))
    )
    (net (code "99") (name "/COL6_B") (class "Default")
      (node (ref "CN2") (pin "25") (pinfunction "S_25") (pintype "passive"))
      (node (ref "U22") (pin "12") (pinfunction "~{OUT7}_12") (pintype "open_collector"))
    )
    (net (code "100") (name "/COL6_C") (class "Default")
      (node (ref "CN2") (pin "27") (pinfunction "S_27") (pintype "passive"))
      (node (ref "U22") (pin "10") (pinfunction "~{OUT5}_10") (pintype "open_collector"))
    )
    (net (code "101") (name "/COL6_D") (class "Default")
      (node (ref "CN2") (pin "30") (pinfunction "S_30") (pintype "passive"))
      (node (ref "U22") (pin "7") (pinfunction "~{OUT2}_7") (pintype "open_collector"))
    )
    (net (code "102") (name "/COL6_E") (class "Default")
      (node (ref "CN2") (pin "31") (pinfunction "S_31") (pintype "passive"))
      (node (ref "U22") (pin "6") (pinfunction "~{OUT1}_6") (pintype "open_collector"))
    )
    (net (code "103") (name "/COL6_F") (class "Default")
      (node (ref "CN2") (pin "32") (pinfunction "S_32") (pintype "passive"))
      (node (ref "U22") (pin "5") (pinfunction "~{OUT0}_5") (pintype "open_collector"))
    )
    (net (code "104") (name "/COL6_G") (class "Default")
      (node (ref "CN2") (pin "17") (pinfunction "S_17") (pintype "passive"))
      (node (ref "U21") (pin "12") (pinfunction "~{OUT7}_12") (pintype "open_collector"))
    )
    (net (code "105") (name "/COL6_H") (class "Default")
      (node (ref "CN2") (pin "21") (pinfunction "S_21") (pintype "passive"))
      (node (ref "U21") (pin "8") (pinfunction "~{OUT3}_8") (pintype "open_collector"))
    )
    (net (code "106") (name "/COL6_K") (class "Default")
      (node (ref "CN2") (pin "22") (pinfunction "S_22") (pintype "passive"))
      (node (ref "U21") (pin "7") (pinfunction "~{OUT2}_7") (pintype "open_collector"))
    )
    (net (code "107") (name "/COL6_M") (class "Default")
      (node (ref "CN2") (pin "23") (pinfunction "S_23") (pintype "passive"))
      (node (ref "U21") (pin "6") (pinfunction "~{OUT1}_6") (pintype "open_collector"))
    )
    (net (code "108") (name "/COL6_N") (class "Default")
      (node (ref "CN2") (pin "26") (pinfunction "S_26") (pintype "passive"))
      (node (ref "U22") (pin "11") (pinfunction "~{OUT6}_11") (pintype "open_collector"))
    )
    (net (code "109") (name "/COL6_P") (class "Default")
      (node (ref "CN2") (pin "28") (pinfunction "S_28") (pintype "passive"))
      (node (ref "U22") (pin "9") (pinfunction "~{OUT4}_9") (pintype "open_collector"))
    )
    (net (code "110") (name "/COL6_R") (class "Default")
      (node (ref "CN2") (pin "29") (pinfunction "S_29") (pintype "passive"))
      (node (ref "U22") (pin "8") (pinfunction "~{OUT3}_8") (pintype "open_collector"))
    )
    (net (code "111") (name "/COL6_S") (class "Default")
      (node (ref "CN2") (pin "19") (pinfunction "S_19") (pintype "passive"))
      (node (ref "U21") (pin "10") (pinfunction "~{OUT5}_10") (pintype "open_collector"))
    )
    (net (code "112") (name "/COL6_T") (class "Default")
      (node (ref "CN2") (pin "18") (pinfunction "S_18") (pintype "passive"))
      (node (ref "U21") (pin "11") (pinfunction "~{OUT6}_11") (pintype "open_collector"))
    )
    (net (code "113") (name "/COL6_U") (class "Default")
      (node (ref "CN2") (pin "20") (pinfunction "S_20") (pintype "passive"))
      (node (ref "U21") (pin "9") (pinfunction "~{OUT4}_9") (pintype "open_collector"))
    )
    (net (code "114") (name "/COL7_A") (class "Default")
      (node (ref "CN2") (pin "40") (pinfunction "S_40") (pintype "passive"))
      (node (ref "U23") (pin "5") (pinfunction "~{OUT0}_5") (pintype "open_collector"))
    )
    (net (code "115") (name "/COL7_B") (class "Default")
      (node (ref "CN4") (pin "20") (pinfunction "S_20") (pintype "passive"))
      (node (ref "U24") (pin "12") (pinfunction "~{OUT7}_12") (pintype "open_collector"))
    )
    (net (code "116") (name "/COL7_C") (class "Default")
      (node (ref "CN4") (pin "18") (pinfunction "S_18") (pintype "passive"))
      (node (ref "U24") (pin "10") (pinfunction "~{OUT5}_10") (pintype "open_collector"))
    )
    (net (code "117") (name "/COL7_D") (class "Default")
      (node (ref "CN4") (pin "23") (pinfunction "S_23") (pintype "passive"))
      (node (ref "U24") (pin "7") (pinfunction "~{OUT2}_7") (pintype "open_collector"))
    )
    (net (code "118") (name "/COL7_E") (class "Default")
      (node (ref "CN4") (pin "22") (pinfunction "S_22") (pintype "passive"))
      (node (ref "U24") (pin "6") (pinfunction "~{OUT1}_6") (pintype "open_collector"))
    )
    (net (code "119") (name "/COL7_F") (class "Default")
      (node (ref "CN4") (pin "21") (pinfunction "S_21") (pintype "passive"))
      (node (ref "U24") (pin "5") (pinfunction "~{OUT0}_5") (pintype "open_collector"))
    )
    (net (code "120") (name "/COL7_G") (class "Default")
      (node (ref "CN2") (pin "33") (pinfunction "S_33") (pintype "passive"))
      (node (ref "U23") (pin "12") (pinfunction "~{OUT7}_12") (pintype "open_collector"))
    )
    (net (code "121") (name "/COL7_H") (class "Default")
      (node (ref "CN2") (pin "37") (pinfunction "S_37") (pintype "passive"))
      (node (ref "U23") (pin "8") (pinfunction "~{OUT3}_8") (pintype "open_collector"))
    )
    (net (code "122") (name "/COL7_K") (class "Default")
      (node (ref "CN2") (pin "38") (pinfunction "S_38") (pintype "passive"))
      (node (ref "U23") (pin "7") (pinfunction "~{OUT2}_7") (pintype "open_collector"))
    )
    (net (code "123") (name "/COL7_M") (class "Default")
      (node (ref "CN2") (pin "39") (pinfunction "S_39") (pintype "passive"))
      (node (ref "U23") (pin "6") (pinfunction "~{OUT1}_6") (pintype "open_collector"))
    )
    (net (code "124") (name "/COL7_N") (class "Default")
      (node (ref "CN4") (pin "19") (pinfunction "S_19") (pintype "passive"))
      (node (ref "U24") (pin "11") (pinfunction "~{OUT6}_11") (pintype "open_collector"))
    )
    (net (code "125") (name "/COL7_P") (class "Default")
      (node (ref "CN4") (pin "17") (pinfunction "S_17") (pintype "passive"))
      (node (ref "U24") (pin "9") (pinfunction "~{OUT4}_9") (pintype "open_collector"))
    )
    (net (code "126") (name "/COL7_R") (class "Default")
      (node (ref "CN4") (pin "24") (pinfunction "S_24") (pintype "passive"))
      (node (ref "U24") (pin "8") (pinfunction "~{OUT3}_8") (pintype "open_collector"))
    )
    (net (code "127") (name "/COL7_S") (class "Default")
      (node (ref "CN2") (pin "35") (pinfunction "S_35") (pintype "passive"))
      (node (ref "U23") (pin "10") (pinfunction "~{OUT5}_10") (pintype "open_collector"))
    )
    (net (code "128") (name "/COL7_T") (class "Default")
      (node (ref "CN2") (pin "34") (pinfunction "S_34") (pintype "passive"))
      (node (ref "U23") (pin "11") (pinfunction "~{OUT6}_11") (pintype "open_collector"))
    )
    (net (code "129") (name "/COL7_U") (class "Default")
      (node (ref "CN2") (pin "36") (pinfunction "S_36") (pintype "passive"))
      (node (ref "U23") (pin "9") (pinfunction "~{OUT4}_9") (pintype "open_collector"))
    )
    (net (code "130") (name "/DP0") (class "Default")
      (node (ref "CN1") (pin "8") (pinfunction "S_8") (pintype "passive"))
      (node (ref "U8") (pin "5") (pinfunction "~{OUT0}_5") (pintype "open_collector"))
    )
    (net (code "131") (name "/DP1") (class "Default")
      (node (ref "CN1") (pin "7") (pinfunction "S_7") (pintype "passive"))
      (node (ref "U8") (pin "6") (pinfunction "~{OUT1}_6") (pintype "open_collector"))
    )
    (net (code "132") (name "/DP2") (class "Default")
      (node (ref "CN1") (pin "6") (pinfunction "S_6") (pintype "passive"))
      (node (ref "U8") (pin "7") (pinfunction "~{OUT2}_7") (pintype "open_collector"))
    )
    (net (code "133") (name "/DP3") (class "Default")
      (node (ref "CN1") (pin "5") (pinfunction "S_5") (pintype "passive"))
      (node (ref "U8") (pin "8") (pinfunction "~{OUT3}_8") (pintype "open_collector"))
    )
    (net (code "134") (name "/DP4") (class "Default")
      (node (ref "CN1") (pin "4") (pinfunction "S_4") (pintype "passive"))
      (node (ref "U8") (pin "9") (pinfunction "~{OUT4}_9") (pintype "open_collector"))
    )
    (net (code "135") (name "/DP5") (class "Default")
      (node (ref "CN1") (pin "3") (pinfunction "S_3") (pintype "passive"))
      (node (ref "U8") (pin "10") (pinfunction "~{OUT5}_10") (pintype "open_collector"))
    )
    (net (code "136") (name "/DP6") (class "Default")
      (node (ref "CN1") (pin "2") (pinfunction "S_2") (pintype "passive"))
      (node (ref "U8") (pin "11") (pinfunction "~{OUT6}_11") (pintype "open_collector"))
    )
    (net (code "137") (name "/DP7") (class "Default")
      (node (ref "CN1") (pin "1") (pinfunction "S_1") (pintype "passive"))
      (node (ref "U8") (pin "12") (pinfunction "~{OUT7}_12") (pintype "open_collector"))
    )
    (net (code "138") (name "/N$1") (class "Default")
      (node (ref "U10") (pin "3") (pinfunction "CLK_3") (pintype "input"))
      (node (ref "U11") (pin "3") (pinfunction "CLK_3") (pintype "input"))
      (node (ref "U12") (pin "3") (pinfunction "CLK_3") (pintype "input"))
      (node (ref "U13") (pin "3") (pinfunction "CLK_3") (pintype "input"))
      (node (ref "U14") (pin "3") (pinfunction "CLK_3") (pintype "input"))
      (node (ref "U15") (pin "3") (pinfunction "CLK_3") (pintype "input"))
      (node (ref "U16") (pin "3") (pinfunction "CLK_3") (pintype "input"))
      (node (ref "U17") (pin "3") (pinfunction "CLK_3") (pintype "input"))
      (node (ref "U18") (pin "3") (pinfunction "CLK_3") (pintype "input"))
      (node (ref "U19") (pin "3") (pinfunction "CLK_3") (pintype "input"))
      (node (ref "U20") (pin "3") (pinfunction "CLK_3") (pintype "input"))
      (node (ref "U21") (pin "3") (pinfunction "CLK_3") (pintype "input"))
      (node (ref "U22") (pin "3") (pinfunction "CLK_3") (pintype "input"))
      (node (ref "U23") (pin "3") (pinfunction "CLK_3") (pintype "input"))
      (node (ref "U24") (pin "3") (pinfunction "CLK_3") (pintype "input"))
      (node (ref "U3") (pin "19") (pinfunction "P=Q_19") (pintype "output"))
      (node (ref "U4") (pin "6") (pinfunction "O_6") (pintype "output"))
      (node (ref "U5") (pin "2") (pinfunction "I1_2") (pintype "input"))
      (node (ref "U8") (pin "3") (pinfunction "CLK_3") (pintype "input"))
      (node (ref "U9") (pin "3") (pinfunction "CLK_3") (pintype "input"))
    )
    (net (code "139") (name "/SCK") (class "Default")
      (node (ref "U1") (pin "5") (pinfunction "IO2_5") (pintype "bidirectional"))
      (node (ref "U4") (pin "4") (pinfunction "I0_4") (pintype "input"))
    )
    (net (code "140") (name "/SDO") (class "Default")
      (node (ref "U1") (pin "4") (pinfunction "IO1_4") (pintype "bidirectional"))
      (node (ref "U8") (pin "2") (pinfunction "SDI_2") (pintype "input"))
    )
    (net (code "141") (name "/~{CPLD_CS}") (class "Default")
      (node (ref "U1") (pin "6") (pinfunction "IO3_6") (pintype "bidirectional"))
      (node (ref "U2") (pin "19") (pinfunction "P=Q_19") (pintype "output"))
    )
    (net (code "142") (name "/~{CTRL_WR}") (class "Default")
      (node (ref "U4") (pin "9") (pinfunction "I0_9") (pintype "input"))
      (node (ref "U5") (pin "3") (pinfunction "O_3") (pintype "output"))
      (node (ref "U6") (pin "11") (pinfunction "C_11") (pintype "input"))
    )
    (net (code "143") (name "/~{IORQ}") (class "Default")
      (node (ref "BUS") (pin "9") (pinfunction "S_9") (pintype "passive"))
      (node (ref "U4") (pin "1") (pinfunction "I0_1") (pintype "input"))
    )
    (net (code "144") (name "/~{RESET}") (class "Default")
      (node (ref "BUS") (pin "6") (pinfunction "S_6") (pintype "passive"))
      (node (ref "U1") (pin "1") (pinfunction "GCLR/_1") (pintype "input"))
      (node (ref "U5") (pin "1") (pinfunction "I0_1") (pintype "input"))
    )
    (net (code "145") (name "/~{WR}") (class "Default")
      (node (ref "BUS") (pin "7") (pinfunction "S_7") (pintype "passive"))
      (node (ref "U4") (pin "2") (pinfunction "I1_2") (pintype "input"))
    )
    (net (code "146") (name "A0") (class "Default")
      (node (ref "BUS") (pin "40") (pinfunction "S_40") (pintype "passive"))
      (node (ref "U2") (pin "2") (pinfunction "P0_2") (pintype "input"))
      (node (ref "U3") (pin "2") (pinfunction "P0_2") (pintype "input"))
    )
    (net (code "147") (name "A1") (class "Default")
      (node (ref "BUS") (pin "39") (pinfunction "S_39") (pintype "passive"))
      (node (ref "U2") (pin "17") (pinfunction "P7_17") (pintype "input"))
      (node (ref "U3") (pin "17") (pinfunction "P7_17") (pintype "input"))
    )
    (net (code "148") (name "A2") (class "Default")
      (node (ref "BUS") (pin "38") (pinfunction "S_38") (pintype "passive"))
      (node (ref "U2") (pin "4") (pinfunction "P1_4") (pintype "input"))
      (node (ref "U3") (pin "4") (pinfunction "P1_4") (pintype "input"))
    )
    (net (code "149") (name "A3") (class "Default")
      (node (ref "BUS") (pin "37") (pinfunction "S_37") (pintype "passive"))
      (node (ref "U2") (pin "15") (pinfunction "P6_15") (pintype "input"))
      (node (ref "U3") (pin "15") (pinfunction "P6_15") (pintype "input"))
    )
    (net (code "150") (name "A4") (class "Default")
      (node (ref "BUS") (pin "36") (pinfunction "S_36") (pintype "passive"))
      (node (ref "U2") (pin "6") (pinfunction "P2_6") (pintype "input"))
      (node (ref "U3") (pin "6") (pinfunction "P2_6") (pintype "input"))
    )
    (net (code "151") (name "A5") (class "Default")
      (node (ref "BUS") (pin "35") (pinfunction "S_35") (pintype "passive"))
      (node (ref "U2") (pin "13") (pinfunction "P5_13") (pintype "input"))
      (node (ref "U3") (pin "13") (pinfunction "P5_13") (pintype "input"))
    )
    (net (code "152") (name "A6") (class "Default")
      (node (ref "BUS") (pin "34") (pinfunction "S_34") (pintype "passive"))
      (node (ref "U2") (pin "8") (pinfunction "P3_8") (pintype "input"))
      (node (ref "U3") (pin "8") (pinfunction "P3_8") (pintype "input"))
    )
    (net (code "153") (name "A7") (class "Default")
      (node (ref "BUS") (pin "33") (pinfunction "S_33") (pintype "passive"))
      (node (ref "U2") (pin "11") (pinfunction "P4_11") (pintype "input"))
      (node (ref "U3") (pin "11") (pinfunction "P4_11") (pintype "input"))
    )
    (net (code "154") (name "CLK") (class "Default")
      (node (ref "BUS") (pin "5") (pinfunction "S_5") (pintype "passive"))
      (node (ref "U1") (pin "43") (pinfunction "GCLK1_43") (pintype "input"))
    )
    (net (code "155") (name "D0") (class "Default")
      (node (ref "BUS") (pin "30") (pinfunction "S_30") (pintype "passive"))
      (node (ref "U1") (pin "18") (pinfunction "IO13_18") (pintype "bidirectional"))
      (node (ref "U6") (pin "2") (pinfunction "1D_2") (pintype "input"))
    )
    (net (code "156") (name "D1") (class "Default")
      (node (ref "BUS") (pin "29") (pinfunction "S_29") (pintype "passive"))
      (node (ref "U1") (pin "19") (pinfunction "IO14_19") (pintype "bidirectional"))
      (node (ref "U6") (pin "3") (pinfunction "2D_3") (pintype "input"))
    )
    (net (code "157") (name "D2") (class "Default")
      (node (ref "BUS") (pin "28") (pinfunction "S_28") (pintype "passive"))
      (node (ref "U1") (pin "20") (pinfunction "IO15_20") (pintype "bidirectional"))
      (node (ref "U6") (pin "4") (pinfunction "3D_4") (pintype "input"))
    )
    (net (code "158") (name "D3") (class "Default")
      (node (ref "BUS") (pin "27") (pinfunction "S_27") (pintype "passive"))
      (node (ref "U1") (pin "21") (pinfunction "IO16_21") (pintype "bidirectional"))
      (node (ref "U6") (pin "5") (pinfunction "4D_5") (pintype "input"))
    )
    (net (code "159") (name "D4") (class "Default")
      (node (ref "BUS") (pin "26") (pinfunction "S_26") (pintype "passive"))
      (node (ref "U1") (pin "24") (pinfunction "IO32_24") (pintype "bidirectional"))
      (node (ref "U6") (pin "6") (pinfunction "5D_6") (pintype "input"))
    )
    (net (code "160") (name "D5") (class "Default")
      (node (ref "BUS") (pin "25") (pinfunction "S_25") (pintype "passive"))
      (node (ref "U1") (pin "25") (pinfunction "IO31_25") (pintype "bidirectional"))
      (node (ref "U6") (pin "7") (pinfunction "6D_7") (pintype "input"))
    )
    (net (code "161") (name "D6") (class "Default")
      (node (ref "BUS") (pin "24") (pinfunction "S_24") (pintype "passive"))
      (node (ref "U1") (pin "26") (pinfunction "IO30_26") (pintype "bidirectional"))
      (node (ref "U6") (pin "8") (pinfunction "7D_8") (pintype "input"))
    )
    (net (code "162") (name "D7") (class "Default")
      (node (ref "BUS") (pin "23") (pinfunction "S_23") (pintype "passive"))
      (node (ref "U1") (pin "27") (pinfunction "IO29_27") (pintype "bidirectional"))
      (node (ref "U6") (pin "9") (pinfunction "8D_9") (pintype "input"))
    )
    (net (code "163") (name "GND") (class "Default")
      (node (ref "BUS") (pin "1") (pinfunction "S_1") (pintype "passive"))
      (node (ref "BUS") (pin "3") (pinfunction "S_3") (pintype "passive"))
      (node (ref "BUS") (pin "31") (pinfunction "S_31") (pintype "passive"))
      (node (ref "BUS") (pin "32") (pinfunction "S_32") (pintype "passive"))
      (node (ref "C1") (pin "-") (pinfunction "-_-") (pintype "passive"))
      (node (ref "C10") (pin "2") (pinfunction "2_2") (pintype "passive"))
      (node (ref "C11") (pin "2") (pinfunction "2_2") (pintype "passive"))
      (node (ref "C12") (pin "2") (pinfunction "2_2") (pintype "passive"))
      (node (ref "C13") (pin "2") (pinfunction "2_2") (pintype "passive"))
      (node (ref "C14") (pin "2") (pinfunction "2_2") (pintype "passive"))
      (node (ref "C15") (pin "2") (pinfunction "2_2") (pintype "passive"))
      (node (ref "C16") (pin "2") (pinfunction "2_2") (pintype "passive"))
      (node (ref "C17") (pin "2") (pinfunction "2_2") (pintype "passive"))
      (node (ref "C18") (pin "2") (pinfunction "2_2") (pintype "passive"))
      (node (ref "C19") (pin "2") (pinfunction "2_2") (pintype "passive"))
      (node (ref "C2") (pin "2") (pinfunction "2_2") (pintype "passive"))
      (node (ref "C20") (pin "2") (pinfunction "2_2") (pintype "passive"))
      (node (ref "C21") (pin "2") (pinfunction "2_2") (pintype "passive"))
      (node (ref "C22") (pin "2") (pinfunction "2_2") (pintype "passive"))
      (node (ref "C23") (pin "2") (pinfunction "2_2") (pintype "passive"))
      (node (ref "C24") (pin "2") (pinfunction "2_2") (pintype "passive"))
      (node (ref "C25") (pin "2") (pinfunction "2_2") (pintype "passive"))
      (node (ref "C26") (pin "2") (pinfunction "2_2") (pintype "passive"))
      (node (ref "C27") (pin "2") (pinfunction "2_2") (pintype "passive"))
      (node (ref "C28") (pin "2") (pinfunction "2_2") (pintype "passive"))
      (node (ref "C3") (pin "2") (pinfunction "2_2") (pintype "passive"))
      (node (ref "C4") (pin "2") (pinfunction "2_2") (pintype "passive"))
      (node (ref "C5") (pin "2") (pinfunction "2_2") (pintype "passive"))
      (node (ref "C6") (pin "2") (pinfunction "2_2") (pintype "passive"))
      (node (ref "C7") (pin "2") (pinfunction "2_2") (pintype "passive"))
      (node (ref "C8") (pin "2") (pinfunction "2_2") (pintype "passive"))
      (node (ref "C9") (pin "2") (pinfunction "2_2") (pintype "passive"))
      (node (ref "CN4") (pin "37") (pinfunction "S_37") (pintype "passive"))
      (node (ref "CN4") (pin "39") (pinfunction "S_39") (pintype "passive"))
      (node (ref "JTAG") (pin "10") (pinfunction "S_10") (pintype "passive"))
      (node (ref "JTAG") (pin "2") (pinfunction "S_2") (pintype "passive"))
      (node (ref "R1") (pin "1") (pinfunction "1_1") (pintype "passive"))
      (node (ref "R10") (pin "1") (pinfunction "1_1") (pintype "passive"))
      (node (ref "R11") (pin "1") (pinfunction "1_1") (pintype "passive"))
      (node (ref "R12") (pin "1") (pinfunction "1_1") (pintype "passive"))
      (node (ref "R13") (pin "1") (pinfunction "1_1") (pintype "passive"))
      (node (ref "R14") (pin "1") (pinfunction "1_1") (pintype "passive"))
      (node (ref "R15") (pin "1") (pinfunction "1_1") (pintype "passive"))
      (node (ref "R16") (pin "1") (pinfunction "1_1") (pintype "passive"))
      (node (ref "R17") (pin "1") (pinfunction "1_1") (pintype "passive"))
      (node (ref "R18") (pin "1") (pinfunction "1_1") (pintype "passive"))
      (node (ref "R21") (pin "1") (pinfunction "1_1") (pintype "passive"))
      (node (ref "R3") (pin "1") (pinfunction "1_1") (pintype "passive"))
      (node (ref "R4") (pin "1") (pinfunction "1_1") (pintype "passive"))
      (node (ref "R5") (pin "1") (pinfunction "1_1") (pintype "passive"))
      (node (ref "R6") (pin "1") (pinfunction "1_1") (pintype "passive"))
      (node (ref "R7") (pin "1") (pinfunction "1_1") (pintype "passive"))
      (node (ref "R8") (pin "1") (pinfunction "1_1") (pintype "passive"))
      (node (ref "R9") (pin "1") (pinfunction "1_1") (pintype "passive"))
      (node (ref "U1") (pin "10") (pinfunction "GND_10") (pintype "power_in"))
      (node (ref "U1") (pin "22") (pinfunction "GND_22") (pintype "power_in"))
      (node (ref "U1") (pin "30") (pinfunction "GND_30") (pintype "power_in"))
      (node (ref "U1") (pin "42") (pinfunction "GND_42") (pintype "power_in"))
      (node (ref "U10") (pin "1") (pinfunction "GND_1") (pintype "power_in"))
      (node (ref "U10") (pin "13") (pinfunction "~{OE}_13") (pintype "input"))
      (node (ref "U11") (pin "1") (pinfunction "GND_1") (pintype "power_in"))
      (node (ref "U11") (pin "13") (pinfunction "~{OE}_13") (pintype "input"))
      (node (ref "U12") (pin "1") (pinfunction "GND_1") (pintype "power_in"))
      (node (ref "U12") (pin "13") (pinfunction "~{OE}_13") (pintype "input"))
      (node (ref "U13") (pin "1") (pinfunction "GND_1") (pintype "power_in"))
      (node (ref "U13") (pin "13") (pinfunction "~{OE}_13") (pintype "input"))
      (node (ref "U14") (pin "1") (pinfunction "GND_1") (pintype "power_in"))
      (node (ref "U14") (pin "13") (pinfunction "~{OE}_13") (pintype "input"))
      (node (ref "U15") (pin "1") (pinfunction "GND_1") (pintype "power_in"))
      (node (ref "U15") (pin "13") (pinfunction "~{OE}_13") (pintype "input"))
      (node (ref "U16") (pin "1") (pinfunction "GND_1") (pintype "power_in"))
      (node (ref "U16") (pin "13") (pinfunction "~{OE}_13") (pintype "input"))
      (node (ref "U17") (pin "1") (pinfunction "GND_1") (pintype "power_in"))
      (node (ref "U17") (pin "13") (pinfunction "~{OE}_13") (pintype "input"))
      (node (ref "U18") (pin "1") (pinfunction "GND_1") (pintype "power_in"))
      (node (ref "U18") (pin "13") (pinfunction "~{OE}_13") (pintype "input"))
      (node (ref "U19") (pin "1") (pinfunction "GND_1") (pintype "power_in"))
      (node (ref "U19") (pin "13") (pinfunction "~{OE}_13") (pintype "input"))
      (node (ref "U2") (pin "10") (pinfunction "GND_10") (pintype "power_in"))
      (node (ref "U2") (pin "12") (pinfunction "Q4_12") (pintype "input"))
      (node (ref "U2") (pin "16") (pinfunction "Q6_16") (pintype "input"))
      (node (ref "U2") (pin "18") (pinfunction "Q7_18") (pintype "input"))
      (node (ref "U2") (pin "3") (pinfunction "Q0_3") (pintype "input"))
      (node (ref "U2") (pin "5") (pinfunction "Q1_5") (pintype "input"))
      (node (ref "U2") (pin "7") (pinfunction "Q2_7") (pintype "input"))
      (node (ref "U2") (pin "9") (pinfunction "Q3_9") (pintype "input"))
      (node (ref "U20") (pin "1") (pinfunction "GND_1") (pintype "power_in"))
      (node (ref "U20") (pin "13") (pinfunction "~{OE}_13") (pintype "input"))
      (node (ref "U21") (pin "1") (pinfunction "GND_1") (pintype "power_in"))
      (node (ref "U21") (pin "13") (pinfunction "~{OE}_13") (pintype "input"))
      (node (ref "U22") (pin "1") (pinfunction "GND_1") (pintype "power_in"))
      (node (ref "U22") (pin "13") (pinfunction "~{OE}_13") (pintype "input"))
      (node (ref "U23") (pin "1") (pinfunction "GND_1") (pintype "power_in"))
      (node (ref "U23") (pin "13") (pinfunction "~{OE}_13") (pintype "input"))
      (node (ref "U24") (pin "1") (pinfunction "GND_1") (pintype "power_in"))
      (node (ref "U24") (pin "13") (pinfunction "~{OE}_13") (pintype "input"))
      (node (ref "U3") (pin "10") (pinfunction "GND_10") (pintype "power_in"))
      (node (ref "U3") (pin "12") (pinfunction "Q4_12") (pintype "input"))
      (node (ref "U3") (pin "16") (pinfunction "Q6_16") (pintype "input"))
      (node (ref "U3") (pin "18") (pinfunction "Q7_18") (pintype "input"))
      (node (ref "U3") (pin "5") (pinfunction "Q1_5") (pintype "input"))
      (node (ref "U3") (pin "7") (pinfunction "Q2_7") (pintype "input"))
      (node (ref "U3") (pin "9") (pinfunction "Q3_9") (pintype "input"))
      (node (ref "U4") (pin "10") (pinfunction "I1_10") (pintype "input"))
      (node (ref "U4") (pin "12") (pinfunction "I0_12") (pintype "input"))
      (node (ref "U4") (pin "13") (pinfunction "I1_13") (pintype "input"))
      (node (ref "U4") (pin "5") (pinfunction "I1_5") (pintype "input"))
      (node (ref "U4") (pin "7") (pinfunction "GND_7") (pintype "power_in"))
      (node (ref "U5") (pin "10") (pinfunction "I1_10") (pintype "input"))
      (node (ref "U5") (pin "12") (pinfunction "I0_12") (pintype "input"))
      (node (ref "U5") (pin "13") (pinfunction "I1_13") (pintype "input"))
      (node (ref "U5") (pin "4") (pinfunction "I0_4") (pintype "input"))
      (node (ref "U5") (pin "5") (pinfunction "I1_5") (pintype "input"))
      (node (ref "U5") (pin "7") (pinfunction "GND_7") (pintype "power_in"))
      (node (ref "U5") (pin "9") (pinfunction "I0_9") (pintype "input"))
      (node (ref "U6") (pin "1") (pinfunction "OC_1") (pintype "input"))
      (node (ref "U6") (pin "10") (pinfunction "GND_10") (pintype "power_in"))
      (node (ref "U7") (pin "3") (pinfunction "C_3") (pintype "input"))
      (node (ref "U7") (pin "4") (pinfunction "G2A_4") (pintype "input"))
      (node (ref "U7") (pin "5") (pinfunction "G2B_5") (pintype "input"))
      (node (ref "U7") (pin "8") (pinfunction "GND_8") (pintype "power_in"))
      (node (ref "U8") (pin "1") (pinfunction "GND_1") (pintype "power_in"))
      (node (ref "U8") (pin "13") (pinfunction "~{OE}_13") (pintype "input"))
      (node (ref "U9") (pin "1") (pinfunction "GND_1") (pintype "power_in"))
      (node (ref "U9") (pin "13") (pinfunction "~{OE}_13") (pintype "input"))
    )
    (net (code "164") (name "Net-(CN4AB-S)") (class "Default")
      (node (ref "CN4") (pin "34") (pinfunction "S_34") (pintype "passive"))
      (node (ref "U7") (pin "14") (pinfunction "Y1_14") (pintype "output"))
    )
    (net (code "165") (name "Net-(CN4AC-S)") (class "Default")
      (node (ref "CN4") (pin "35") (pinfunction "S_35") (pintype "passive"))
      (node (ref "U7") (pin "13") (pinfunction "Y2_13") (pintype "output"))
    )
    (net (code "166") (name "Net-(CN4AD-S)") (class "Default")
      (node (ref "CN4") (pin "36") (pinfunction "S_36") (pintype "passive"))
      (node (ref "U7") (pin "12") (pinfunction "Y3_12") (pintype "output"))
    )
    (net (code "167") (name "Net-(U2A-G)") (class "Default")
      (node (ref "U2") (pin "1") (pinfunction "G_1") (pintype "input"))
      (node (ref "U3") (pin "1") (pinfunction "G_1") (pintype "input"))
      (node (ref "U4") (pin "3") (pinfunction "O_3") (pintype "output"))
    )
    (net (code "168") (name "Net-(U6A-1Q)") (class "Default")
      (node (ref "U6") (pin "19") (pinfunction "1Q_19") (pintype "tri_state"))
      (node (ref "U7") (pin "1") (pinfunction "A_1") (pintype "input"))
    )
    (net (code "169") (name "Net-(U6A-2Q)") (class "Default")
      (node (ref "U6") (pin "18") (pinfunction "2Q_18") (pintype "tri_state"))
      (node (ref "U7") (pin "2") (pinfunction "B_2") (pintype "input"))
    )
    (net (code "170") (name "Net-(U8A-R-EXT)") (class "Default")
      (node (ref "R1") (pin "2") (pinfunction "2_2") (pintype "passive"))
      (node (ref "U8") (pin "15") (pinfunction "R-EXT_15") (pintype "input"))
    )
    (net (code "171") (name "Net-(U8A-SDO)") (class "Default")
      (node (ref "U8") (pin "14") (pinfunction "SDO_14") (pintype "output"))
      (node (ref "U9") (pin "2") (pinfunction "SDI_2") (pintype "input"))
    )
    (net (code "172") (name "Net-(U9A-R-EXT)") (class "Default")
      (node (ref "R3") (pin "2") (pinfunction "2_2") (pintype "passive"))
      (node (ref "U9") (pin "15") (pinfunction "R-EXT_15") (pintype "input"))
    )
    (net (code "173") (name "Net-(U10A-LE)") (class "Default")
      (node (ref "U10") (pin "4") (pinfunction "LE_4") (pintype "input"))
      (node (ref "U11") (pin "4") (pinfunction "LE_4") (pintype "input"))
      (node (ref "U12") (pin "4") (pinfunction "LE_4") (pintype "input"))
      (node (ref "U13") (pin "4") (pinfunction "LE_4") (pintype "input"))
      (node (ref "U14") (pin "4") (pinfunction "LE_4") (pintype "input"))
      (node (ref "U15") (pin "4") (pinfunction "LE_4") (pintype "input"))
      (node (ref "U16") (pin "4") (pinfunction "LE_4") (pintype "input"))
      (node (ref "U17") (pin "4") (pinfunction "LE_4") (pintype "input"))
      (node (ref "U18") (pin "4") (pinfunction "LE_4") (pintype "input"))
      (node (ref "U19") (pin "4") (pinfunction "LE_4") (pintype "input"))
      (node (ref "U20") (pin "4") (pinfunction "LE_4") (pintype "input"))
      (node (ref "U21") (pin "4") (pinfunction "LE_4") (pintype "input"))
      (node (ref "U22") (pin "4") (pinfunction "LE_4") (pintype "input"))
      (node (ref "U23") (pin "4") (pinfunction "LE_4") (pintype "input"))
      (node (ref "U24") (pin "4") (pinfunction "LE_4") (pintype "input"))
      (node (ref "U4") (pin "8") (pinfunction "O_8") (pintype "output"))
      (node (ref "U8") (pin "4") (pinfunction "LE_4") (pintype "input"))
      (node (ref "U9") (pin "4") (pinfunction "LE_4") (pintype "input"))
    )
    (net (code "174") (name "Net-(U10A-R-EXT)") (class "Default")
      (node (ref "R4") (pin "2") (pinfunction "2_2") (pintype "passive"))
      (node (ref "U10") (pin "15") (pinfunction "R-EXT_15") (pintype "input"))
    )
    (net (code "175") (name "Net-(U10A-SDI)") (class "Default")
      (node (ref "U10") (pin "2") (pinfunction "SDI_2") (pintype "input"))
      (node (ref "U9") (pin "14") (pinfunction "SDO_14") (pintype "output"))
    )
    (net (code "176") (name "Net-(U10A-SDO)") (class "Default")
      (node (ref "U10") (pin "14") (pinfunction "SDO_14") (pintype "output"))
      (node (ref "U11") (pin "2") (pinfunction "SDI_2") (pintype "input"))
    )
    (net (code "177") (name "Net-(U11A-R-EXT)") (class "Default")
      (node (ref "R5") (pin "2") (pinfunction "2_2") (pintype "passive"))
      (node (ref "U11") (pin "15") (pinfunction "R-EXT_15") (pintype "input"))
    )
    (net (code "178") (name "Net-(U11A-SDO)") (class "Default")
      (node (ref "U11") (pin "14") (pinfunction "SDO_14") (pintype "output"))
      (node (ref "U12") (pin "2") (pinfunction "SDI_2") (pintype "input"))
    )
    (net (code "179") (name "Net-(U12A-R-EXT)") (class "Default")
      (node (ref "R6") (pin "2") (pinfunction "2_2") (pintype "passive"))
      (node (ref "U12") (pin "15") (pinfunction "R-EXT_15") (pintype "input"))
    )
    (net (code "180") (name "Net-(U12A-SDO)") (class "Default")
      (node (ref "U12") (pin "14") (pinfunction "SDO_14") (pintype "output"))
      (node (ref "U13") (pin "2") (pinfunction "SDI_2") (pintype "input"))
    )
    (net (code "181") (name "Net-(U13A-R-EXT)") (class "Default")
      (node (ref "R7") (pin "2") (pinfunction "2_2") (pintype "passive"))
      (node (ref "U13") (pin "15") (pinfunction "R-EXT_15") (pintype "input"))
    )
    (net (code "182") (name "Net-(U13A-SDO)") (class "Default")
      (node (ref "U13") (pin "14") (pinfunction "SDO_14") (pintype "output"))
      (node (ref "U14") (pin "2") (pinfunction "SDI_2") (pintype "input"))
    )
    (net (code "183") (name "Net-(U14A-R-EXT)") (class "Default")
      (node (ref "R8") (pin "2") (pinfunction "2_2") (pintype "passive"))
      (node (ref "U14") (pin "15") (pinfunction "R-EXT_15") (pintype "input"))
    )
    (net (code "184") (name "Net-(U14A-SDO)") (class "Default")
      (node (ref "U14") (pin "14") (pinfunction "SDO_14") (pintype "output"))
      (node (ref "U15") (pin "2") (pinfunction "SDI_2") (pintype "input"))
    )
    (net (code "185") (name "Net-(U15A-R-EXT)") (class "Default")
      (node (ref "R9") (pin "2") (pinfunction "2_2") (pintype "passive"))
      (node (ref "U15") (pin "15") (pinfunction "R-EXT_15") (pintype "input"))
    )
    (net (code "186") (name "Net-(U15A-SDO)") (class "Default")
      (node (ref "U15") (pin "14") (pinfunction "SDO_14") (pintype "output"))
      (node (ref "U16") (pin "2") (pinfunction "SDI_2") (pintype "input"))
    )
    (net (code "187") (name "Net-(U16A-R-EXT)") (class "Default")
      (node (ref "R10") (pin "2") (pinfunction "2_2") (pintype "passive"))
      (node (ref "U16") (pin "15") (pinfunction "R-EXT_15") (pintype "input"))
    )
    (net (code "188") (name "Net-(U16A-SDO)") (class "Default")
      (node (ref "U16") (pin "14") (pinfunction "SDO_14") (pintype "output"))
      (node (ref "U17") (pin "2") (pinfunction "SDI_2") (pintype "input"))
    )
    (net (code "189") (name "Net-(U17A-R-EXT)") (class "Default")
      (node (ref "R11") (pin "2") (pinfunction "2_2") (pintype "passive"))
      (node (ref "U17") (pin "15") (pinfunction "R-EXT_15") (pintype "input"))
    )
    (net (code "190") (name "Net-(U17A-SDO)") (class "Default")
      (node (ref "U17") (pin "14") (pinfunction "SDO_14") (pintype "output"))
      (node (ref "U18") (pin "2") (pinfunction "SDI_2") (pintype "input"))
    )
    (net (code "191") (name "Net-(U18A-R-EXT)") (class "Default")
      (node (ref "R12") (pin "2") (pinfunction "2_2") (pintype "passive"))
      (node (ref "U18") (pin "15") (pinfunction "R-EXT_15") (pintype "input"))
    )
    (net (code "192") (name "Net-(U18A-SDO)") (class "Default")
      (node (ref "U18") (pin "14") (pinfunction "SDO_14") (pintype "output"))
      (node (ref "U19") (pin "2") (pinfunction "SDI_2") (pintype "input"))
    )
    (net (code "193") (name "Net-(U19A-R-EXT)") (class "Default")
      (node (ref "R13") (pin "2") (pinfunction "2_2") (pintype "passive"))
      (node (ref "U19") (pin "15") (pinfunction "R-EXT_15") (pintype "input"))
    )
    (net (code "194") (name "Net-(U19A-SDO)") (class "Default")
      (node (ref "U19") (pin "14") (pinfunction "SDO_14") (pintype "output"))
      (node (ref "U20") (pin "2") (pinfunction "SDI_2") (pintype "input"))
    )
    (net (code "195") (name "Net-(U20A-R-EXT)") (class "Default")
      (node (ref "R14") (pin "2") (pinfunction "2_2") (pintype "passive"))
      (node (ref "U20") (pin "15") (pinfunction "R-EXT_15") (pintype "input"))
    )
    (net (code "196") (name "Net-(U20A-SDO)") (class "Default")
      (node (ref "U20") (pin "14") (pinfunction "SDO_14") (pintype "output"))
      (node (ref "U21") (pin "2") (pinfunction "SDI_2") (pintype "input"))
    )
    (net (code "197") (name "Net-(U21A-R-EXT)") (class "Default")
      (node (ref "R15") (pin "2") (pinfunction "2_2") (pintype "passive"))
      (node (ref "U21") (pin "15") (pinfunction "R-EXT_15") (pintype "input"))
    )
    (net (code "198") (name "Net-(U21A-SDO)") (class "Default")
      (node (ref "U21") (pin "14") (pinfunction "SDO_14") (pintype "output"))
      (node (ref "U22") (pin "2") (pinfunction "SDI_2") (pintype "input"))
    )
    (net (code "199") (name "Net-(U22A-R-EXT)") (class "Default")
      (node (ref "R16") (pin "2") (pinfunction "2_2") (pintype "passive"))
      (node (ref "U22") (pin "15") (pinfunction "R-EXT_15") (pintype "input"))
    )
    (net (code "200") (name "Net-(U22A-SDO)") (class "Default")
      (node (ref "U22") (pin "14") (pinfunction "SDO_14") (pintype "output"))
      (node (ref "U23") (pin "2") (pinfunction "SDI_2") (pintype "input"))
    )
    (net (code "201") (name "Net-(U23A-R-EXT)") (class "Default")
      (node (ref "R17") (pin "2") (pinfunction "2_2") (pintype "passive"))
      (node (ref "U23") (pin "15") (pinfunction "R-EXT_15") (pintype "input"))
    )
    (net (code "202") (name "Net-(U23A-SDO)") (class "Default")
      (node (ref "U23") (pin "14") (pinfunction "SDO_14") (pintype "output"))
      (node (ref "U24") (pin "2") (pinfunction "SDI_2") (pintype "input"))
    )
    (net (code "203") (name "Net-(U24A-R-EXT)") (class "Default")
      (node (ref "R18") (pin "2") (pinfunction "2_2") (pintype "passive"))
      (node (ref "U24") (pin "15") (pinfunction "R-EXT_15") (pintype "input"))
    )
    (net (code "204") (name "TCK") (class "Default")
      (node (ref "JTAG") (pin "1") (pinfunction "S_1") (pintype "passive"))
      (node (ref "R21") (pin "2") (pinfunction "2_2") (pintype "passive"))
      (node (ref "U1") (pin "32") (pinfunction "IO20/TCK_32") (pintype "bidirectional"))
    )
    (net (code "205") (name "TDI") (class "Default")
      (node (ref "JTAG") (pin "9") (pinfunction "S_9") (pintype "passive"))
      (node (ref "R20") (pin "1") (pinfunction "1_1") (pintype "passive"))
      (node (ref "U1") (pin "7") (pinfunction "IO4/TDI_7") (pintype "bidirectional"))
    )
    (net (code "206") (name "TDO") (class "Default")
      (node (ref "JTAG") (pin "3") (pinfunction "S_3") (pintype "passive"))
      (node (ref "U1") (pin "38") (pinfunction "IO25/TDO_38") (pintype "bidirectional"))
    )
    (net (code "207") (name "TMS") (class "Default")
      (node (ref "JTAG") (pin "5") (pinfunction "S_5") (pintype "passive"))
      (node (ref "R19") (pin "1") (pinfunction "1_1") (pintype "passive"))
      (node (ref "U1") (pin "13") (pinfunction "IO9/TMS_13") (pintype "bidirectional"))
    )
    (net (code "208") (name "unconnected-(BUSAM-S-Pad8)") (class "Default")
      (node (ref "BUS") (pin "8") (pinfunction "S_8") (pintype "passive"))
    )
    (net (code "209") (name "unconnected-(BUSB-S-Pad10)") (class "Default")
      (node (ref "BUS") (pin "10") (pinfunction "S_10") (pintype "passive"))
    )
    (net (code "210") (name "unconnected-(BUSC-S-Pad11)") (class "Default")
      (node (ref "BUS") (pin "11") (pinfunction "S_11") (pintype "passive"))
    )
    (net (code "211") (name "unconnected-(BUSD-S-Pad12)") (class "Default")
      (node (ref "BUS") (pin "12") (pinfunction "S_12") (pintype "passive"))
    )
    (net (code "212") (name "unconnected-(BUSE-S-Pad13)") (class "Default")
      (node (ref "BUS") (pin "13") (pinfunction "S_13") (pintype "passive"))
    )
    (net (code "213") (name "unconnected-(BUSF-S-Pad14)") (class "Default")
      (node (ref "BUS") (pin "14") (pinfunction "S_14") (pintype "passive"))
    )
    (net (code "214") (name "unconnected-(BUSG-S-Pad15)") (class "Default")
      (node (ref "BUS") (pin "15") (pinfunction "S_15") (pintype "passive"))
    )
    (net (code "215") (name "unconnected-(BUSH-S-Pad16)") (class "Default")
      (node (ref "BUS") (pin "16") (pinfunction "S_16") (pintype "passive"))
    )
    (net (code "216") (name "unconnected-(BUSI-S-Pad17)") (class "Default")
      (node (ref "BUS") (pin "17") (pinfunction "S_17") (pintype "passive"))
    )
    (net (code "217") (name "unconnected-(BUSJ-S-Pad18)") (class "Default")
      (node (ref "BUS") (pin "18") (pinfunction "S_18") (pintype "passive"))
    )
    (net (code "218") (name "unconnected-(BUSK-S-Pad19)") (class "Default")
      (node (ref "BUS") (pin "19") (pinfunction "S_19") (pintype "passive"))
    )
    (net (code "219") (name "unconnected-(BUSM-S-Pad20)") (class "Default")
      (node (ref "BUS") (pin "20") (pinfunction "S_20") (pintype "passive"))
    )
    (net (code "220") (name "unconnected-(BUSN-S-Pad21)") (class "Default")
      (node (ref "BUS") (pin "21") (pinfunction "S_21") (pintype "passive"))
    )
    (net (code "221") (name "unconnected-(BUSO-S-Pad22)") (class "Default")
      (node (ref "BUS") (pin "22") (pinfunction "S_22") (pintype "passive"))
    )
    (net (code "222") (name "unconnected-(CN3I-S-Pad17)") (class "Default")
      (node (ref "CN3") (pin "17") (pinfunction "S_17") (pintype "passive"))
    )
    (net (code "223") (name "unconnected-(CN3J-S-Pad18)") (class "Default")
      (node (ref "CN3") (pin "18") (pinfunction "S_18") (pintype "passive"))
    )
    (net (code "224") (name "unconnected-(CN3K-S-Pad19)") (class "Default")
      (node (ref "CN3") (pin "19") (pinfunction "S_19") (pintype "passive"))
    )
    (net (code "225") (name "unconnected-(CN3M-S-Pad20)") (class "Default")
      (node (ref "CN3") (pin "20") (pinfunction "S_20") (pintype "passive"))
    )
    (net (code "226") (name "unconnected-(CN3N-S-Pad21)") (class "Default")
      (node (ref "CN3") (pin "21") (pinfunction "S_21") (pintype "passive"))
    )
    (net (code "227") (name "unconnected-(CN3O-S-Pad22)") (class "Default")
      (node (ref "CN3") (pin "22") (pinfunction "S_22") (pintype "passive"))
    )
    (net (code "228") (name "unconnected-(CN3P-S-Pad23)") (class "Default")
      (node (ref "CN3") (pin "23") (pinfunction "S_23") (pintype "passive"))
    )
    (net (code "229") (name "unconnected-(CN3Q-S-Pad24)") (class "Default")
      (node (ref "CN3") (pin "24") (pinfunction "S_24") (pintype "passive"))
    )
    (net (code "230") (name "unconnected-(CN4AA-S-Pad33)") (class "Default")
      (node (ref "CN4") (pin "33") (pinfunction "S_33") (pintype "passive"))
    )
    (net (code "231") (name "unconnected-(CN4R-S-Pad25)") (class "Default")
      (node (ref "CN4") (pin "25") (pinfunction "S_25") (pintype "passive"))
    )
    (net (code "232") (name "unconnected-(CN4S-S-Pad26)") (class "Default")
      (node (ref "CN4") (pin "26") (pinfunction "S_26") (pintype "passive"))
    )
    (net (code "233") (name "unconnected-(CN4T-S-Pad27)") (class "Default")
      (node (ref "CN4") (pin "27") (pinfunction "S_27") (pintype "passive"))
    )
    (net (code "234") (name "unconnected-(CN4U-S-Pad28)") (class "Default")
      (node (ref "CN4") (pin "28") (pinfunction "S_28") (pintype "passive"))
    )
    (net (code "235") (name "unconnected-(CN4V-S-Pad29)") (class "Default")
      (node (ref "CN4") (pin "29") (pinfunction "S_29") (pintype "passive"))
    )
    (net (code "236") (name "unconnected-(CN4X-S-Pad30)") (class "Default")
      (node (ref "CN4") (pin "30") (pinfunction "S_30") (pintype "passive"))
    )
    (net (code "237") (name "unconnected-(CN4Y-S-Pad31)") (class "Default")
      (node (ref "CN4") (pin "31") (pinfunction "S_31") (pintype "passive"))
    )
    (net (code "238") (name "unconnected-(CN4Z-S-Pad32)") (class "Default")
      (node (ref "CN4") (pin "32") (pinfunction "S_32") (pintype "passive"))
    )
    (net (code "239") (name "unconnected-(JTAGG-S-Pad6)") (class "Default")
      (node (ref "JTAG") (pin "6") (pinfunction "S_6") (pintype "passive"))
    )
    (net (code "240") (name "unconnected-(JTAGH-S-Pad7)") (class "Default")
      (node (ref "JTAG") (pin "7") (pinfunction "S_7") (pintype "passive"))
    )
    (net (code "241") (name "unconnected-(JTAGI-S-Pad8)") (class "Default")
      (node (ref "JTAG") (pin "8") (pinfunction "S_8") (pintype "passive"))
    )
    (net (code "242") (name "unconnected-(U1B-IO5-Pad8)") (class "Default")
      (node (ref "U1") (pin "8") (pinfunction "IO5_8") (pintype "bidirectional"))
    )
    (net (code "243") (name "unconnected-(U1B-IO6-Pad9)") (class "Default")
      (node (ref "U1") (pin "9") (pinfunction "IO6_9") (pintype "bidirectional"))
    )
    (net (code "244") (name "unconnected-(U1B-IO7-Pad11)") (class "Default")
      (node (ref "U1") (pin "11") (pinfunction "IO7_11") (pintype "bidirectional"))
    )
    (net (code "245") (name "unconnected-(U1B-IO8-Pad12)") (class "Default")
      (node (ref "U1") (pin "12") (pinfunction "IO8_12") (pintype "bidirectional"))
    )
    (net (code "246") (name "unconnected-(U1B-IO10-Pad14)") (class "Default")
      (node (ref "U1") (pin "14") (pinfunction "IO10_14") (pintype "bidirectional"))
    )
    (net (code "247") (name "unconnected-(U1B-IO11-Pad16)") (class "Default")
      (node (ref "U1") (pin "16") (pinfunction "IO11_16") (pintype "bidirectional"))
    )
    (net (code "248") (name "unconnected-(U1B-IO12-Pad17)") (class "Default")
      (node (ref "U1") (pin "17") (pinfunction "IO12_17") (pintype "bidirectional"))
    )
    (net (code "249") (name "unconnected-(U1B-IO17-Pad41)") (class "Default")
      (node (ref "U1") (pin "41") (pinfunction "IO17_41") (pintype "bidirectional"))
    )
    (net (code "250") (name "unconnected-(U1B-IO18-Pad40)") (class "Default")
      (node (ref "U1") (pin "40") (pinfunction "IO18_40") (pintype "bidirectional"))
    )
    (net (code "251") (name "unconnected-(U1B-IO19-Pad39)") (class "Default")
      (node (ref "U1") (pin "39") (pinfunction "IO19_39") (pintype "bidirectional"))
    )
    (net (code "252") (name "unconnected-(U1B-IO21-Pad37)") (class "Default")
      (node (ref "U1") (pin "37") (pinfunction "IO21_37") (pintype "bidirectional"))
    )
    (net (code "253") (name "unconnected-(U1B-IO22-Pad36)") (class "Default")
      (node (ref "U1") (pin "36") (pinfunction "IO22_36") (pintype "bidirectional"))
    )
    (net (code "254") (name "unconnected-(U1B-IO23-Pad34)") (class "Default")
      (node (ref "U1") (pin "34") (pinfunction "IO23_34") (pintype "bidirectional"))
    )
    (net (code "255") (name "unconnected-(U1B-IO24-Pad33)") (class "Default")
      (node (ref "U1") (pin "33") (pinfunction "IO24_33") (pintype "bidirectional"))
    )
    (net (code "256") (name "unconnected-(U1B-IO26-Pad31)") (class "Default")
      (node (ref "U1") (pin "31") (pinfunction "IO26_31") (pintype "bidirectional"))
    )
    (net (code "257") (name "unconnected-(U1B-IO27-Pad29)") (class "Default")
      (node (ref "U1") (pin "29") (pinfunction "IO27_29") (pintype "bidirectional"))
    )
    (net (code "258") (name "unconnected-(U1B-IO28-Pad28)") (class "Default")
      (node (ref "U1") (pin "28") (pinfunction "IO28_28") (pintype "bidirectional"))
    )
    (net (code "259") (name "unconnected-(U1B-OE1-Pad44)") (class "Default")
      (node (ref "U1") (pin "44") (pinfunction "OE1_44") (pintype "input"))
    )
    (net (code "260") (name "unconnected-(U1B-OE2-GCLK2-Pad2)") (class "Default")
      (node (ref "U1") (pin "2") (pinfunction "OE2-GCLK2_2") (pintype "input"))
    )
    (net (code "261") (name "unconnected-(U4D-O-Pad11)") (class "Default")
      (node (ref "U4") (pin "11") (pinfunction "O_11") (pintype "output"))
    )
    (net (code "262") (name "unconnected-(U5B-O-Pad6)") (class "Default")
      (node (ref "U5") (pin "6") (pinfunction "O_6") (pintype "output"))
    )
    (net (code "263") (name "unconnected-(U5C-O-Pad8)") (class "Default")
      (node (ref "U5") (pin "8") (pinfunction "O_8") (pintype "output"))
    )
    (net (code "264") (name "unconnected-(U5D-O-Pad11)") (class "Default")
      (node (ref "U5") (pin "11") (pinfunction "O_11") (pintype "output"))
    )
    (net (code "265") (name "unconnected-(U6A-3Q-Pad17)") (class "Default")
      (node (ref "U6") (pin "17") (pinfunction "3Q_17") (pintype "tri_state"))
    )
    (net (code "266") (name "unconnected-(U6A-4Q-Pad16)") (class "Default")
      (node (ref "U6") (pin "16") (pinfunction "4Q_16") (pintype "tri_state"))
    )
    (net (code "267") (name "unconnected-(U6A-5Q-Pad15)") (class "Default")
      (node (ref "U6") (pin "15") (pinfunction "5Q_15") (pintype "tri_state"))
    )
    (net (code "268") (name "unconnected-(U6A-6Q-Pad14)") (class "Default")
      (node (ref "U6") (pin "14") (pinfunction "6Q_14") (pintype "tri_state"))
    )
    (net (code "269") (name "unconnected-(U6A-7Q-Pad13)") (class "Default")
      (node (ref "U6") (pin "13") (pinfunction "7Q_13") (pintype "tri_state"))
    )
    (net (code "270") (name "unconnected-(U6A-8Q-Pad12)") (class "Default")
      (node (ref "U6") (pin "12") (pinfunction "8Q_12") (pintype "tri_state"))
    )
    (net (code "271") (name "unconnected-(U7A-Y0-Pad15)") (class "Default")
      (node (ref "U7") (pin "15") (pinfunction "Y0_15") (pintype "output"))
    )
    (net (code "272") (name "unconnected-(U7A-Y4-Pad11)") (class "Default")
      (node (ref "U7") (pin "11") (pinfunction "Y4_11") (pintype "output"))
    )
    (net (code "273") (name "unconnected-(U7A-Y5-Pad10)") (class "Default")
      (node (ref "U7") (pin "10") (pinfunction "Y5_10") (pintype "output"))
    )
    (net (code "274") (name "unconnected-(U7A-Y6-Pad9)") (class "Default")
      (node (ref "U7") (pin "9") (pinfunction "Y6_9") (pintype "output"))
    )
    (net (code "275") (name "unconnected-(U7A-Y7-Pad7)") (class "Default")
      (node (ref "U7") (pin "7") (pinfunction "Y7_7") (pintype "output"))
    )
    (net (code "276") (name "unconnected-(U24A-SDO-Pad14)") (class "Default")
      (node (ref "U24") (pin "14") (pinfunction "SDO_14") (pintype "output"))
    )
  )
)
